# Modular_RFPA_v104.net
KiCad netlist of a schematic drawn in EAGLE
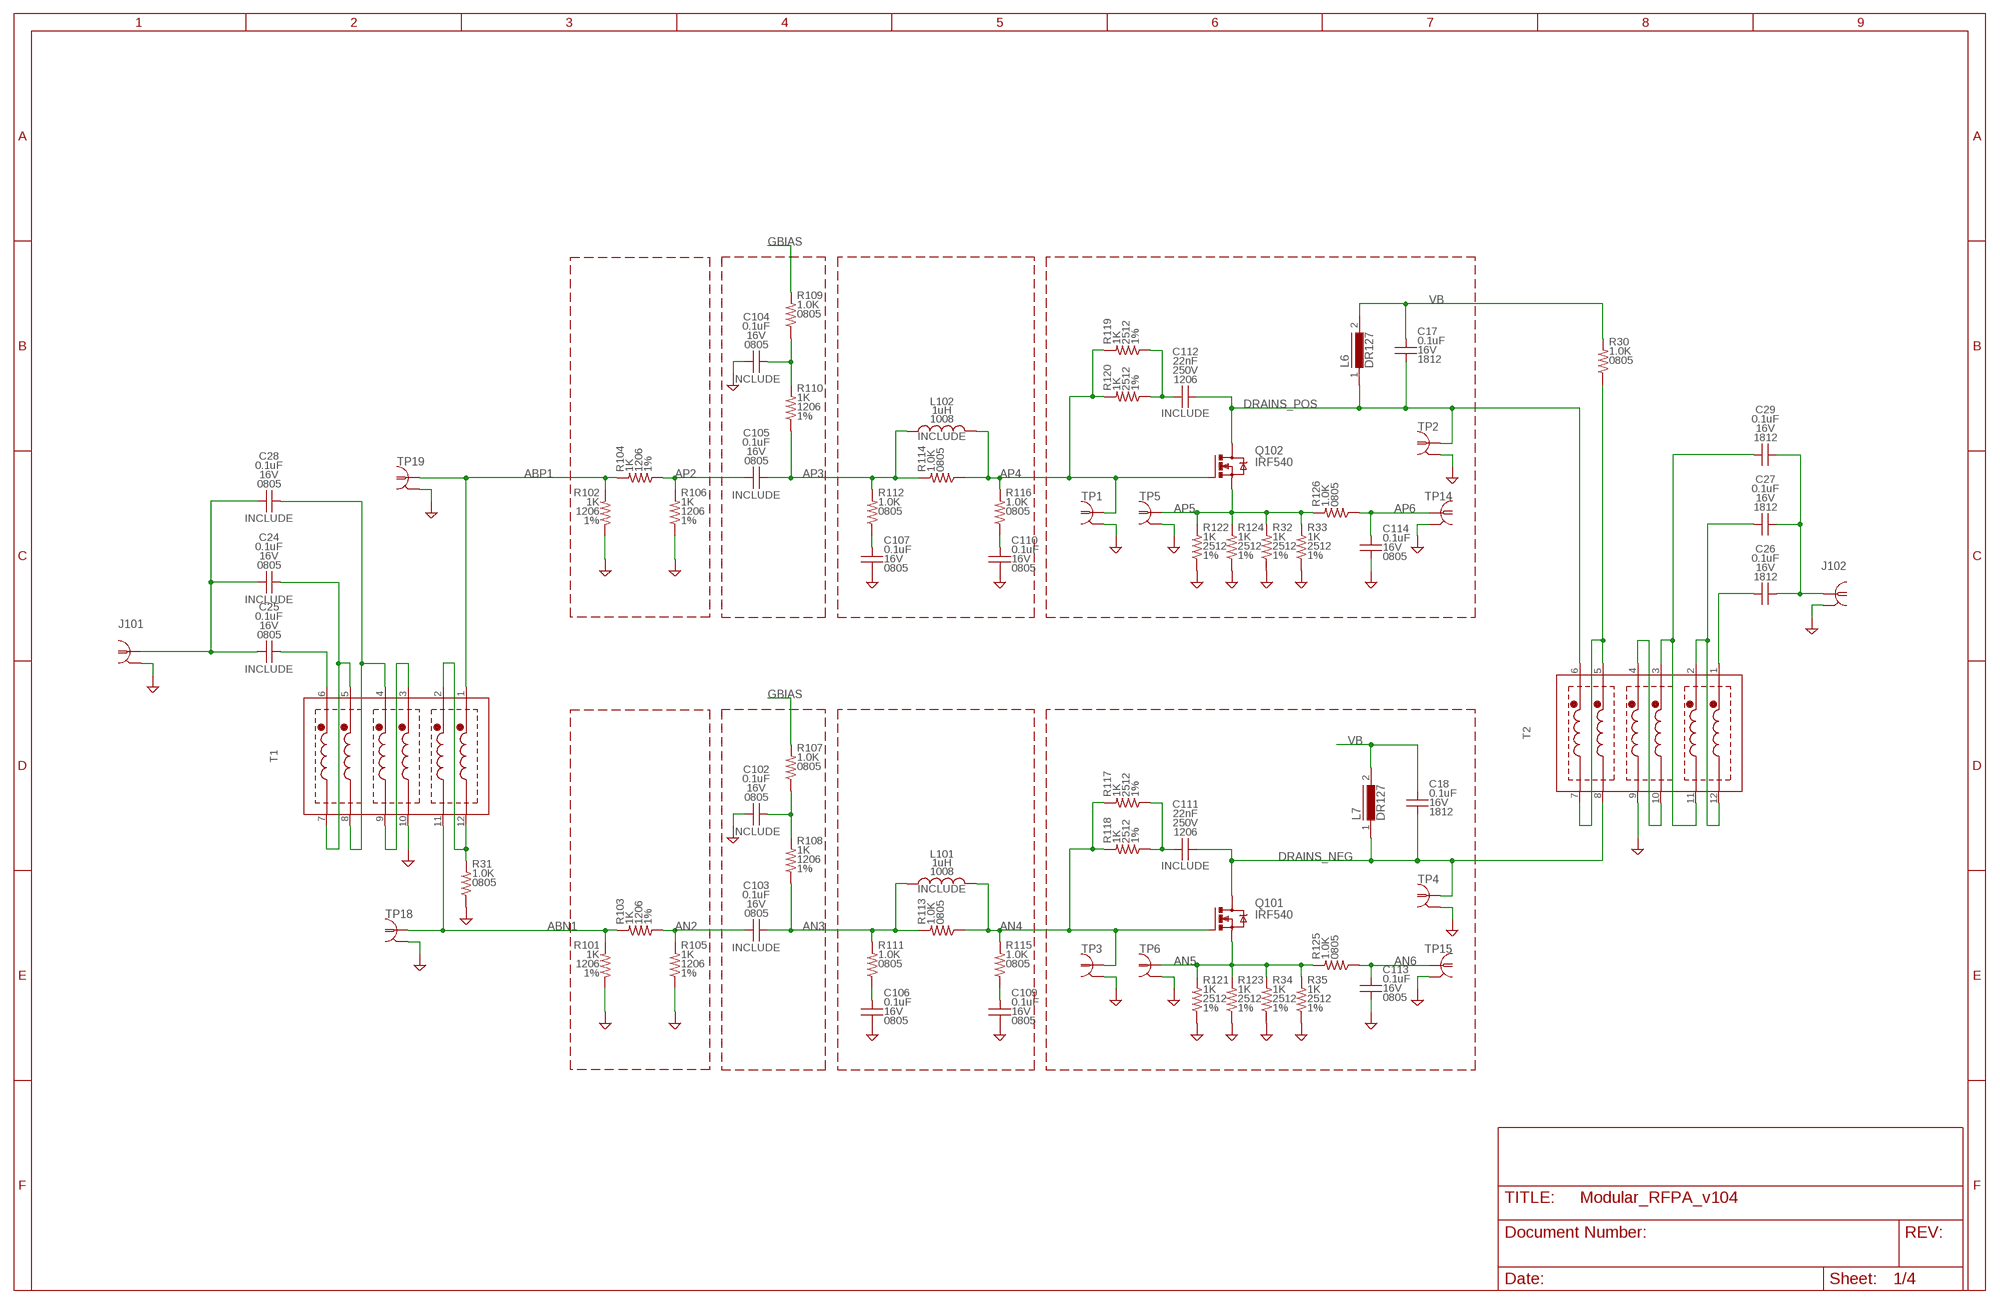
[diagram p0: schematic, sheet 1]
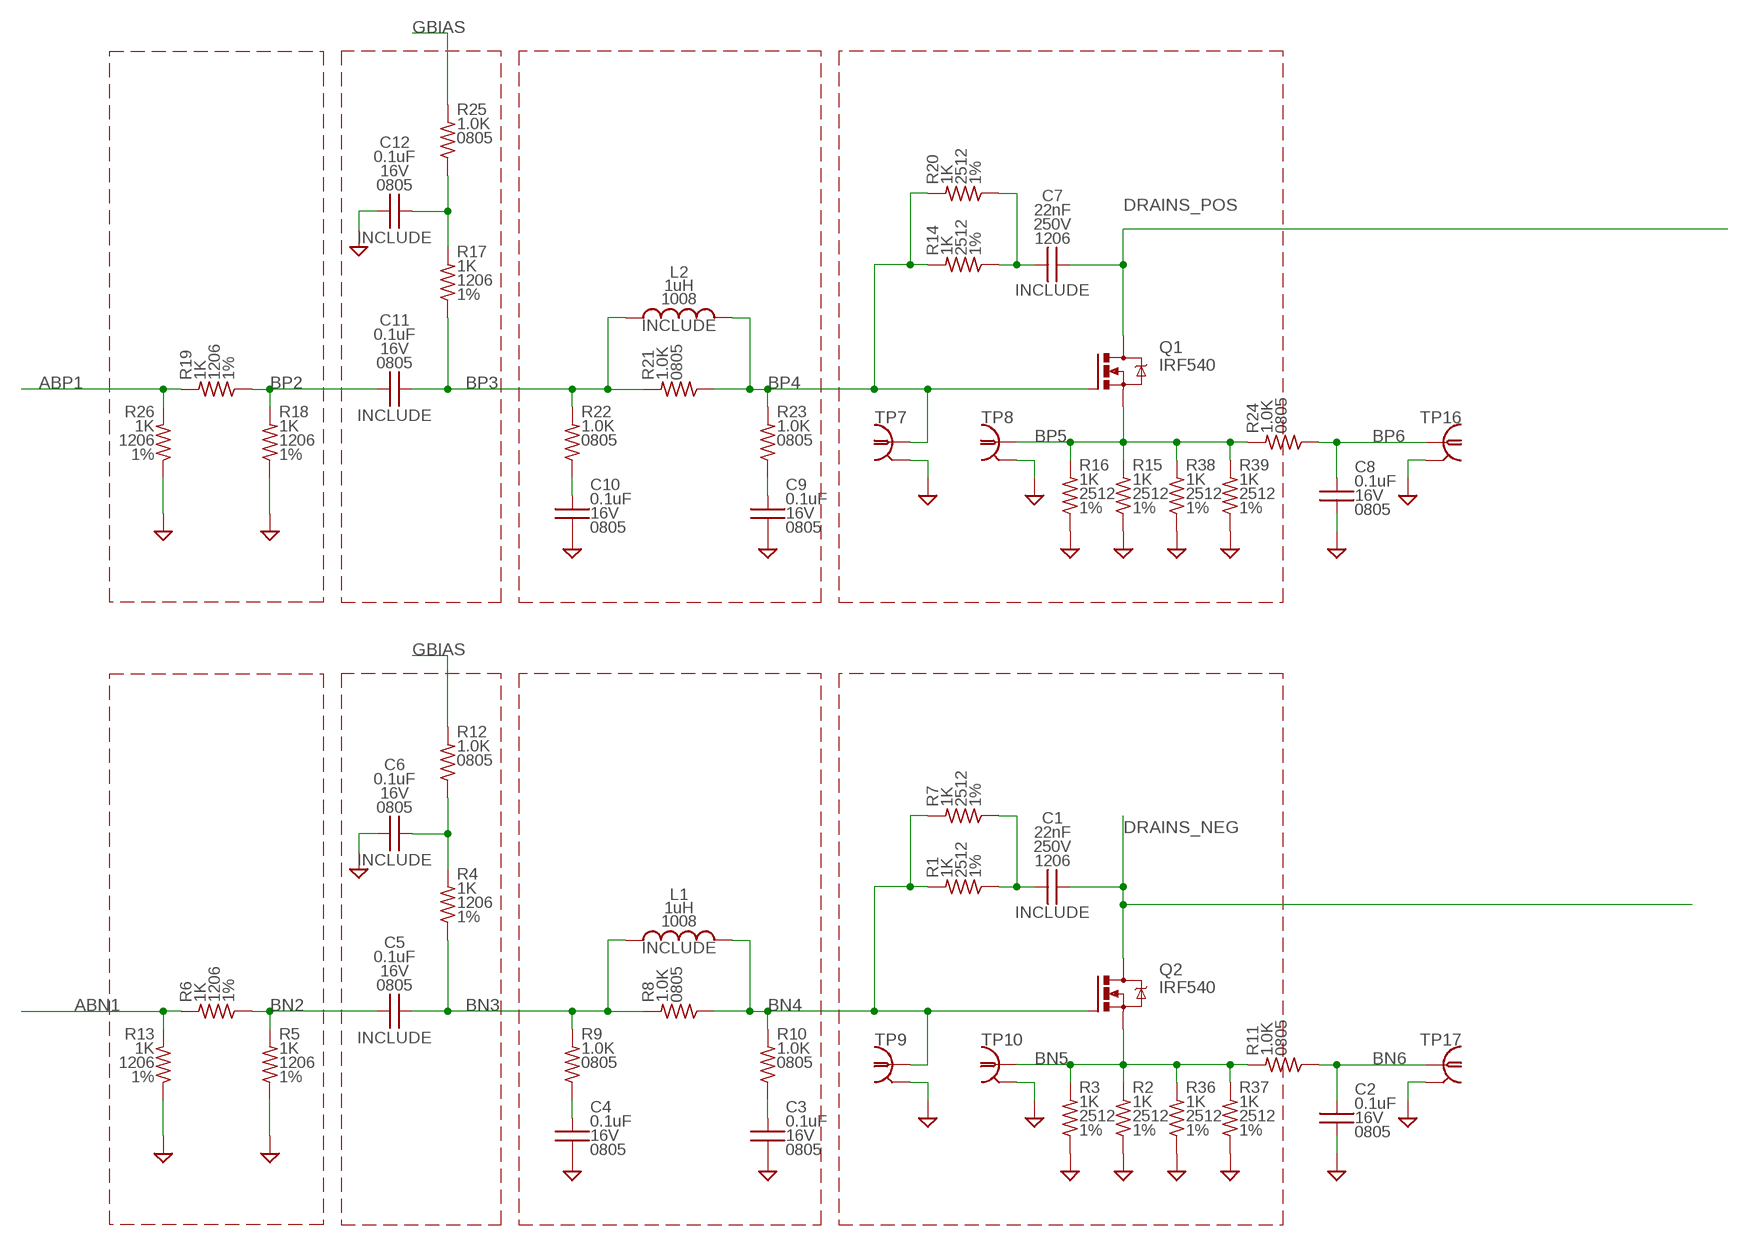
[diagram p1: schematic, sheet 2]
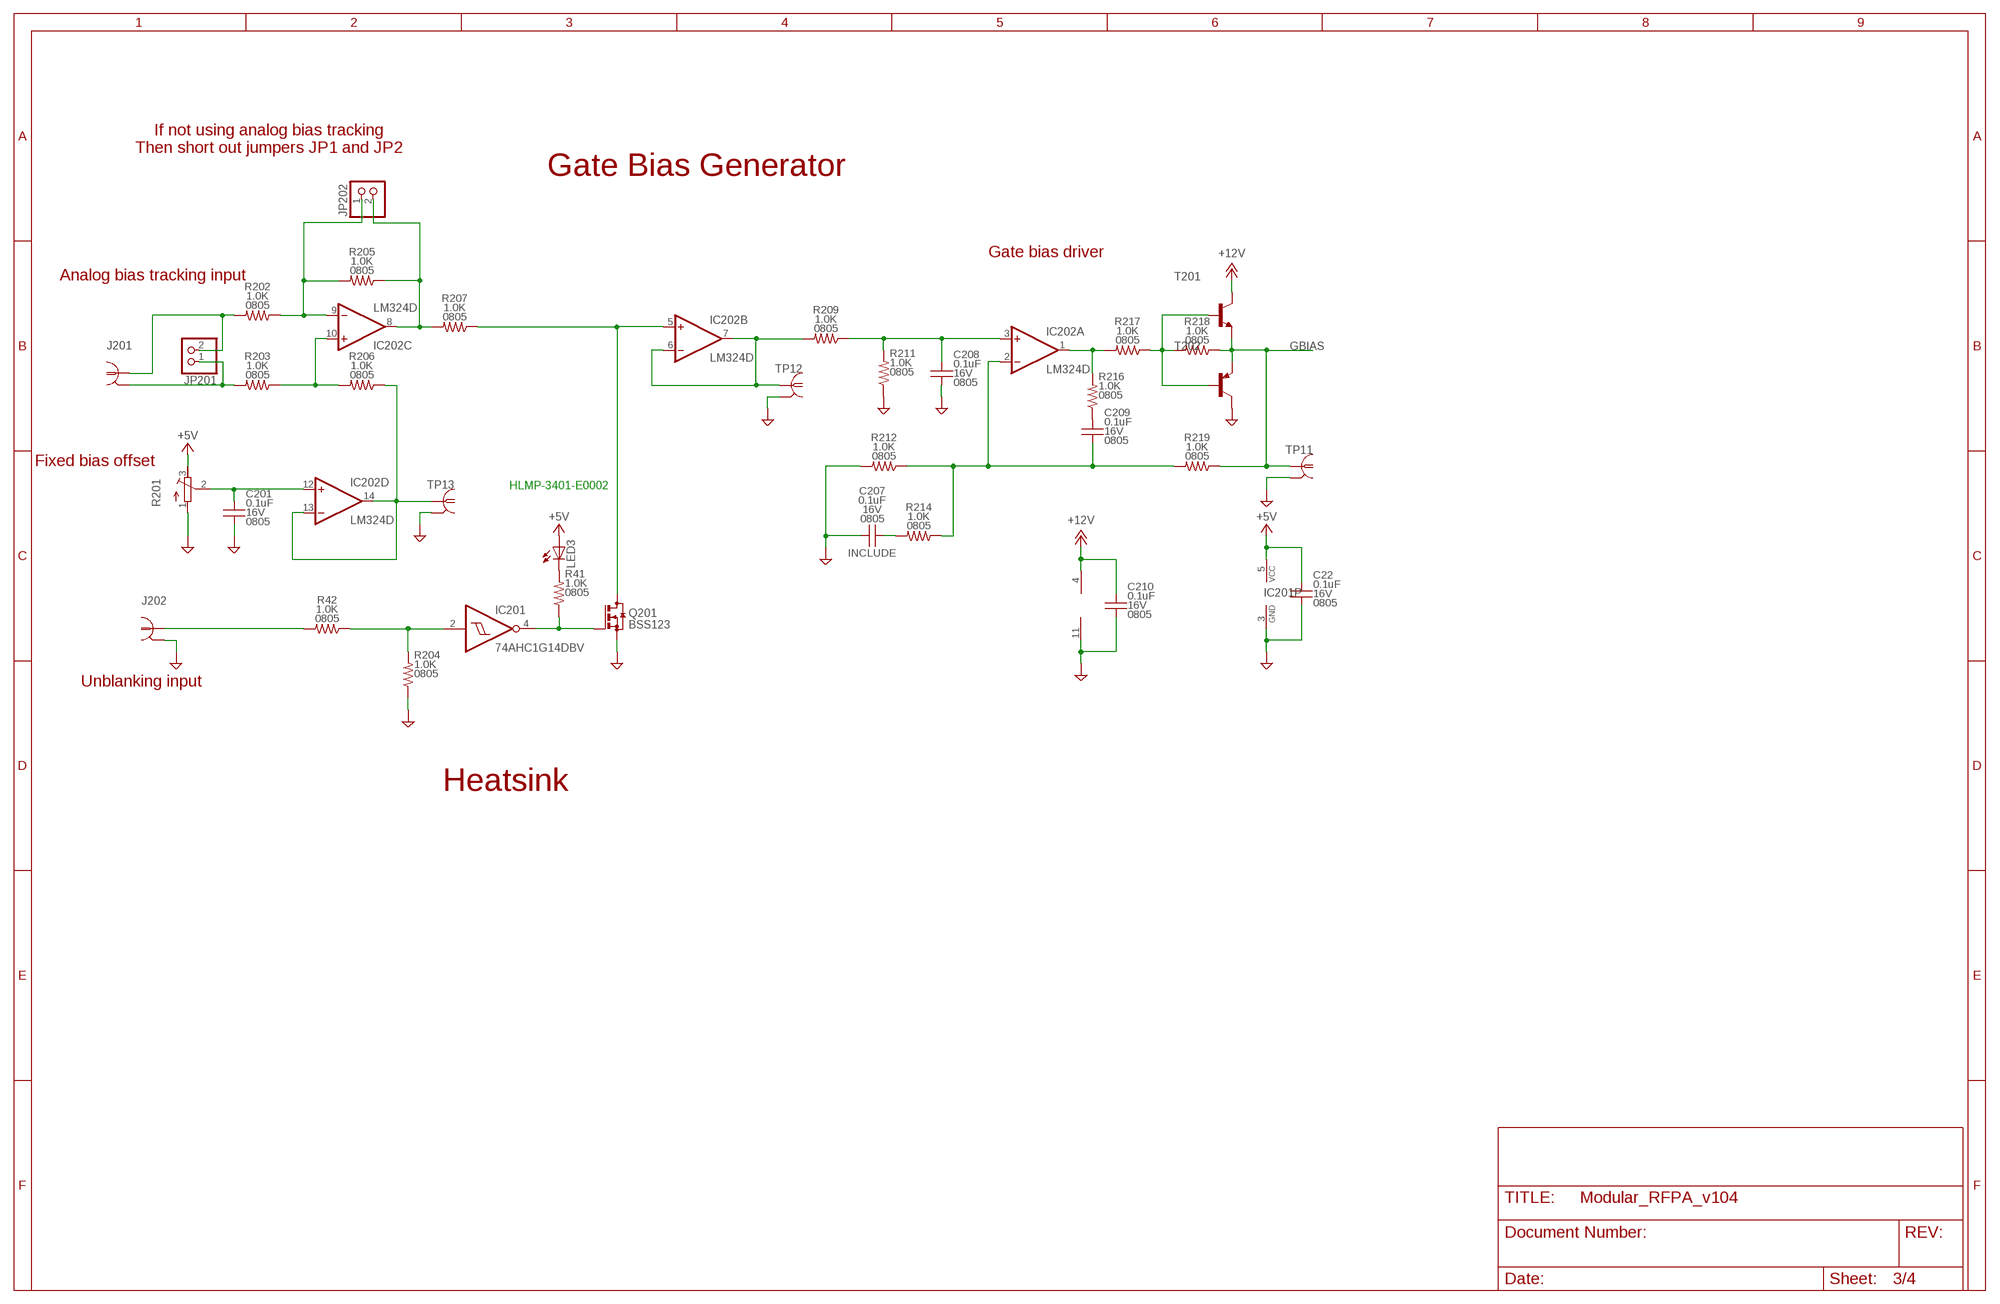
[diagram p2: schematic, sheet 3]
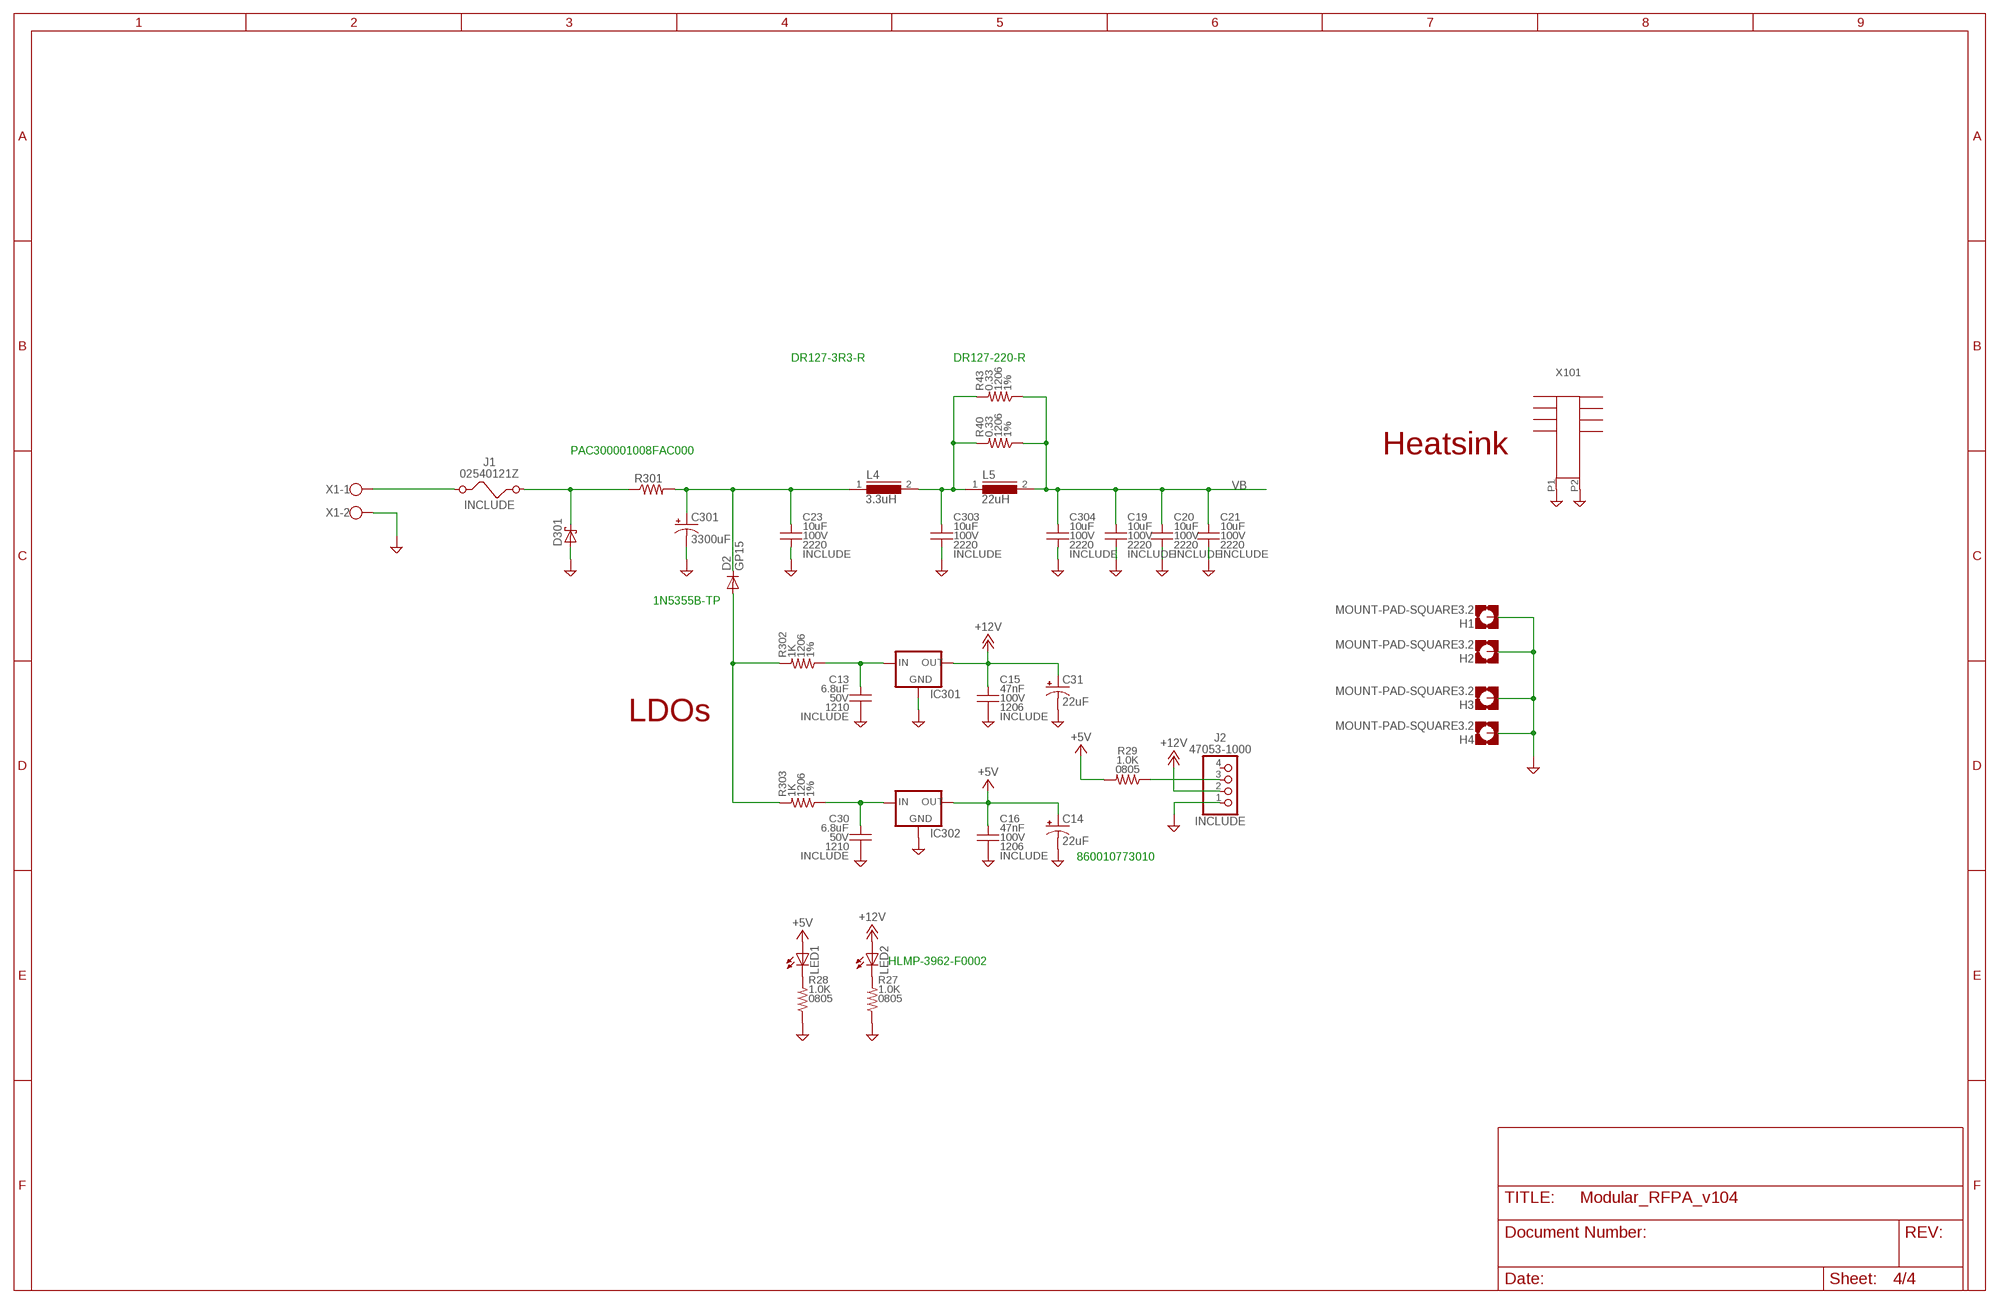
[diagram p3: schematic, sheet 4]

(export (version "E")
  (design (tool "Eeschema 10.0.6"))
  (components
    (comp (ref "C22")
      (value "0.1uF")
      (footprint "eagle-import:0805_IPC-7351B")
      (fields (field (name "VOLTAGE") "16V"))
      (libsource (lib "eagle-import") (part "C0805_IPCC-0.1U-16V-0805-X7R"))
    )
    (comp (ref "C201")
      (value "0.1uF")
      (footprint "eagle-import:0805_IPC-7351B")
      (fields (field (name "VOLTAGE") "16V"))
      (libsource (lib "eagle-import") (part "C0805_IPCC-0.1U-16V-0805-X7R"))
    )
    (comp (ref "C207")
      (value "0.1uF")
      (footprint "eagle-import:0805_IPC-7351B")
      (fields (field (name "PACKAGE") "0805") (field (name "VOLTAGE") "16V") (field (name "BOM") "INCLUDE"))
      (libsource (lib "eagle-import") (part "C0805_IPCC-0.1U-16V-0805-X7R"))
    )
    (comp (ref "C208")
      (value "0.1uF")
      (footprint "eagle-import:0805_IPC-7351B")
      (fields (field (name "VOLTAGE") "16V"))
      (libsource (lib "eagle-import") (part "C0805_IPCC-0.1U-16V-0805-X7R"))
    )
    (comp (ref "C209")
      (value "0.1uF")
      (footprint "eagle-import:0805_IPC-7351B")
      (fields (field (name "VOLTAGE") "16V"))
      (libsource (lib "eagle-import") (part "C0805_IPCC-0.1U-16V-0805-X7R"))
    )
    (comp (ref "C210")
      (value "0.1uF")
      (footprint "eagle-import:0805_IPC-7351B")
      (fields (field (name "VOLTAGE") "16V"))
      (libsource (lib "eagle-import") (part "C0805_IPCC-0.1U-16V-0805-X7R"))
    )
    (comp (ref "IC201")
      (value "74AHC1G14DBV")
      (footprint "eagle-import:SOT23-5")
      (libsource (lib "eagle-import") (part "741G14DBVAHC"))
    )
    (comp (ref "IC202")
      (value "LM324D")
      (footprint "eagle-import:SO14")
      (libsource (lib "eagle-import") (part "LM324D"))
    )
    (comp (ref "J201")
      (value "COAXBNC_EDGE")
      (footprint "eagle-import:BNC_EDGE")
      (libsource (lib "eagle-import") (part "COAXBNC_EDGE"))
    )
    (comp (ref "J202")
      (value "COAXBNC_EDGE")
      (footprint "eagle-import:BNC_EDGE")
      (libsource (lib "eagle-import") (part "COAXBNC_EDGE"))
    )
    (comp (ref "JP201")
      (value "PINHD-1X2")
      (footprint "eagle-import:1X02")
      (libsource (lib "eagle-import") (part "PINHD-1X2"))
    )
    (comp (ref "JP202")
      (value "PINHD-1X2")
      (footprint "eagle-import:1X02")
      (libsource (lib "eagle-import") (part "PINHD-1X2"))
    )
    (comp (ref "LED3")
      (value "LED5MM")
      (footprint "eagle-import:LED5MM")
      (libsource (lib "eagle-import") (part "LED5MM"))
    )
    (comp (ref "Q201")
      (value "BSS123")
      (footprint "eagle-import:SOT23")
      (libsource (lib "eagle-import") (part "BSS123"))
    )
    (comp (ref "R41")
      (value "1.0K")
      (footprint "eagle-import:0805_IPC-7351B")
      (libsource (lib "eagle-import") (part "R0805_IPCR-1.0K-0.1%-0805-0.1W"))
    )
    (comp (ref "R42")
      (value "1.0K")
      (footprint "eagle-import:0805_IPC-7351B")
      (fields (field (name "PACKAGE") "0805"))
      (libsource (lib "eagle-import") (part "R0805_IPCR-1.0K-0.1%-0805-0.1W"))
    )
    (comp (ref "R201")
      (value "R-TRIMM3299W")
      (footprint "eagle-import:RTRIM3299W")
      (libsource (lib "eagle-import") (part "R-TRIMM3299W"))
    )
    (comp (ref "R202")
      (value "1.0K")
      (footprint "eagle-import:0805_IPC-7351B")
      (fields (field (name "PACKAGE") "0805"))
      (libsource (lib "eagle-import") (part "R0805_IPCR-1.0K-0.1%-0805-0.1W"))
    )
    (comp (ref "R203")
      (value "1.0K")
      (footprint "eagle-import:0805_IPC-7351B")
      (fields (field (name "PACKAGE") "0805"))
      (libsource (lib "eagle-import") (part "R0805_IPCR-1.0K-0.1%-0805-0.1W"))
    )
    (comp (ref "R204")
      (value "1.0K")
      (footprint "eagle-import:0805_IPC-7351B")
      (libsource (lib "eagle-import") (part "R0805_IPCR-1.0K-0.1%-0805-0.1W"))
    )
    (comp (ref "R205")
      (value "1.0K")
      (footprint "eagle-import:0805_IPC-7351B")
      (fields (field (name "PACKAGE") "0805"))
      (libsource (lib "eagle-import") (part "R0805_IPCR-1.0K-0.1%-0805-0.1W"))
    )
    (comp (ref "R206")
      (value "1.0K")
      (footprint "eagle-import:0805_IPC-7351B")
      (fields (field (name "PACKAGE") "0805"))
      (libsource (lib "eagle-import") (part "R0805_IPCR-1.0K-0.1%-0805-0.1W"))
    )
    (comp (ref "R207")
      (value "1.0K")
      (footprint "eagle-import:0805_IPC-7351B")
      (fields (field (name "PACKAGE") "0805"))
      (libsource (lib "eagle-import") (part "R0805_IPCR-1.0K-0.1%-0805-0.1W"))
    )
    (comp (ref "R209")
      (value "1.0K")
      (footprint "eagle-import:0805_IPC-7351B")
      (fields (field (name "PACKAGE") "0805"))
      (libsource (lib "eagle-import") (part "R0805_IPCR-1.0K-0.1%-0805-0.1W"))
    )
    (comp (ref "R211")
      (value "1.0K")
      (footprint "eagle-import:0805_IPC-7351B")
      (libsource (lib "eagle-import") (part "R0805_IPCR-1.0K-0.1%-0805-0.1W"))
    )
    (comp (ref "R212")
      (value "1.0K")
      (footprint "eagle-import:0805_IPC-7351B")
      (fields (field (name "PACKAGE") "0805"))
      (libsource (lib "eagle-import") (part "R0805_IPCR-1.0K-0.1%-0805-0.1W"))
    )
    (comp (ref "R214")
      (value "1.0K")
      (footprint "eagle-import:0805_IPC-7351B")
      (fields (field (name "PACKAGE") "0805"))
      (libsource (lib "eagle-import") (part "R0805_IPCR-1.0K-0.1%-0805-0.1W"))
    )
    (comp (ref "R216")
      (value "1.0K")
      (footprint "eagle-import:0805_IPC-7351B")
      (libsource (lib "eagle-import") (part "R0805_IPCR-1.0K-0.1%-0805-0.1W"))
    )
    (comp (ref "R217")
      (value "1.0K")
      (footprint "eagle-import:0805_IPC-7351B")
      (fields (field (name "PACKAGE") "0805"))
      (libsource (lib "eagle-import") (part "R0805_IPCR-1.0K-0.1%-0805-0.1W"))
    )
    (comp (ref "R218")
      (value "1.0K")
      (footprint "eagle-import:0805_IPC-7351B")
      (fields (field (name "PACKAGE") "0805"))
      (libsource (lib "eagle-import") (part "R0805_IPCR-1.0K-0.1%-0805-0.1W"))
    )
    (comp (ref "R219")
      (value "1.0K")
      (footprint "eagle-import:0805_IPC-7351B")
      (fields (field (name "PACKAGE") "0805"))
      (libsource (lib "eagle-import") (part "R0805_IPCR-1.0K-0.1%-0805-0.1W"))
    )
    (comp (ref "T201")
      (value "BC808-NPN-SOT23-BEC")
      (footprint "eagle-import:SOT23-BEC")
      (libsource (lib "eagle-import") (part "-NPN-SOT23-BECBC808"))
    )
    (comp (ref "T202")
      (value "BC807-16-PNP-SOT23-BEC")
      (footprint "eagle-import:SOT23-BEC")
      (libsource (lib "eagle-import") (part "-PNP-SOT23-BECBC807-16"))
    )
    (comp (ref "TP11")
      (value "PROBE_TPTP_5MM")
      (footprint "eagle-import:PROBE_TP_5MM")
      (libsource (lib "eagle-import") (part "PROBE_TPTP_5MM"))
    )
    (comp (ref "TP12")
      (value "PROBE_TPTP_5MM")
      (footprint "eagle-import:PROBE_TP_5MM")
      (libsource (lib "eagle-import") (part "PROBE_TPTP_5MM"))
    )
    (comp (ref "TP13")
      (value "PROBE_TPTP_5MM")
      (footprint "eagle-import:PROBE_TP_5MM")
      (libsource (lib "eagle-import") (part "PROBE_TPTP_5MM"))
    )
    (comp (ref "C1")
      (value "22nF")
      (footprint "eagle-import:C1206")
      (fields
        (field (name "BOM") "INCLUDE")
        (field (name "PACKAGE") "1206")
        (field (name "PARTNO") "C3216NP02E223J160AA")
        (field (name "VOLTAGE") "250V")
      )
      (libsource (lib "eagle-import") (part "CC1206C-22N-250V-5%-1206-NP0"))
    )
    (comp (ref "C2")
      (value "0.1uF")
      (footprint "eagle-import:0805_IPC-7351B")
      (fields (field (name "VOLTAGE") "16V"))
      (libsource (lib "eagle-import") (part "C0805_IPCC-0.1U-16V-0805-X7R"))
    )
    (comp (ref "C3")
      (value "0.1uF")
      (footprint "eagle-import:0805_IPC-7351B")
      (fields (field (name "VOLTAGE") "16V"))
      (libsource (lib "eagle-import") (part "C0805_IPCC-0.1U-16V-0805-X7R"))
    )
    (comp (ref "C4")
      (value "0.1uF")
      (footprint "eagle-import:0805_IPC-7351B")
      (fields (field (name "VOLTAGE") "16V"))
      (libsource (lib "eagle-import") (part "C0805_IPCC-0.1U-16V-0805-X7R"))
    )
    (comp (ref "C5")
      (value "0.1uF")
      (footprint "eagle-import:0805_IPC-7351B")
      (fields (field (name "PACKAGE") "0805") (field (name "VOLTAGE") "16V") (field (name "BOM") "INCLUDE"))
      (libsource (lib "eagle-import") (part "C0805_IPCC-0.1U-16V-0805-X7R"))
    )
    (comp (ref "C6")
      (value "0.1uF")
      (footprint "eagle-import:0805_IPC-7351B")
      (fields (field (name "PACKAGE") "0805") (field (name "VOLTAGE") "16V") (field (name "BOM") "INCLUDE"))
      (libsource (lib "eagle-import") (part "C0805_IPCC-0.1U-16V-0805-X7R"))
    )
    (comp (ref "C7")
      (value "22nF")
      (footprint "eagle-import:C1206")
      (fields
        (field (name "BOM") "INCLUDE")
        (field (name "PACKAGE") "1206")
        (field (name "PARTNO") "C3216NP02E223J160AA")
        (field (name "VOLTAGE") "250V")
      )
      (libsource (lib "eagle-import") (part "CC1206C-22N-250V-5%-1206-NP0"))
    )
    (comp (ref "C8")
      (value "0.1uF")
      (footprint "eagle-import:0805_IPC-7351B")
      (fields (field (name "VOLTAGE") "16V"))
      (libsource (lib "eagle-import") (part "C0805_IPCC-0.1U-16V-0805-X7R"))
    )
    (comp (ref "C9")
      (value "0.1uF")
      (footprint "eagle-import:0805_IPC-7351B")
      (fields (field (name "VOLTAGE") "16V"))
      (libsource (lib "eagle-import") (part "C0805_IPCC-0.1U-16V-0805-X7R"))
    )
    (comp (ref "C10")
      (value "0.1uF")
      (footprint "eagle-import:0805_IPC-7351B")
      (fields (field (name "VOLTAGE") "16V"))
      (libsource (lib "eagle-import") (part "C0805_IPCC-0.1U-16V-0805-X7R"))
    )
    (comp (ref "C11")
      (value "0.1uF")
      (footprint "eagle-import:0805_IPC-7351B")
      (fields (field (name "PACKAGE") "0805") (field (name "VOLTAGE") "16V") (field (name "BOM") "INCLUDE"))
      (libsource (lib "eagle-import") (part "C0805_IPCC-0.1U-16V-0805-X7R"))
    )
    (comp (ref "C12")
      (value "0.1uF")
      (footprint "eagle-import:0805_IPC-7351B")
      (fields (field (name "PACKAGE") "0805") (field (name "VOLTAGE") "16V") (field (name "BOM") "INCLUDE"))
      (libsource (lib "eagle-import") (part "C0805_IPCC-0.1U-16V-0805-X7R"))
    )
    (comp (ref "L1")
      (value "1uH")
      (footprint "eagle-import:L1008")
      (fields (field (name "PARTNO") "1008CS-102XJEC"))
      (libsource (lib "eagle-import") (part "L_CHIP1008L-1.0U-AIR-5%-1008-0.37A"))
    )
    (comp (ref "L2")
      (value "1uH")
      (footprint "eagle-import:L1008")
      (fields (field (name "PARTNO") "1008CS-102XJEC"))
      (libsource (lib "eagle-import") (part "L_CHIP1008L-1.0U-AIR-5%-1008-0.37A"))
    )
    (comp (ref "Q1")
      (value "IRF540")
      (footprint "eagle-import:TO220BV")
      (libsource (lib "eagle-import") (part "IRF540"))
    )
    (comp (ref "Q2")
      (value "IRF540")
      (footprint "eagle-import:TO220BV")
      (libsource (lib "eagle-import") (part "IRF540"))
    )
    (comp (ref "R1")
      (value "1K")
      (footprint "eagle-import:R2512")
      (fields (field (name "POWER") "1"))
      (libsource (lib "eagle-import") (part "RR2512R-1K-1%-2512-1W"))
    )
    (comp (ref "R2")
      (value "1K")
      (footprint "eagle-import:R2512")
      (fields (field (name "POWER") "1"))
      (libsource (lib "eagle-import") (part "RR2512R-1K-1%-2512-1W"))
    )
    (comp (ref "R3")
      (value "1K")
      (footprint "eagle-import:R2512")
      (fields (field (name "POWER") "1"))
      (libsource (lib "eagle-import") (part "RR2512R-1K-1%-2512-1W"))
    )
    (comp (ref "R4")
      (value "1K")
      (footprint "eagle-import:R1206")
      (fields (field (name "POWER") "0.25"))
      (libsource (lib "eagle-import") (part "RR1206R-1.0K-1%-1206-0.25W"))
    )
    (comp (ref "R5")
      (value "1K")
      (footprint "eagle-import:R1206")
      (fields (field (name "POWER") "0.25"))
      (libsource (lib "eagle-import") (part "RR1206R-1.0K-1%-1206-0.25W"))
    )
    (comp (ref "R6")
      (value "1K")
      (footprint "eagle-import:R1206")
      (fields (field (name "POWER") "0.25"))
      (libsource (lib "eagle-import") (part "RR1206R-1.0K-1%-1206-0.25W"))
    )
    (comp (ref "R7")
      (value "1K")
      (footprint "eagle-import:R2512")
      (fields (field (name "POWER") "1"))
      (libsource (lib "eagle-import") (part "RR2512R-1K-1%-2512-1W"))
    )
    (comp (ref "R8")
      (value "1.0K")
      (footprint "eagle-import:0805_IPC-7351B")
      (libsource (lib "eagle-import") (part "R0805_IPCR-1.0K-0.1%-0805-0.1W"))
    )
    (comp (ref "R9")
      (value "1.0K")
      (footprint "eagle-import:0805_IPC-7351B")
      (libsource (lib "eagle-import") (part "R0805_IPCR-1.0K-0.1%-0805-0.1W"))
    )
    (comp (ref "R10")
      (value "1.0K")
      (footprint "eagle-import:0805_IPC-7351B")
      (libsource (lib "eagle-import") (part "R0805_IPCR-1.0K-0.1%-0805-0.1W"))
    )
    (comp (ref "R11")
      (value "1.0K")
      (footprint "eagle-import:0805_IPC-7351B")
      (libsource (lib "eagle-import") (part "R0805_IPCR-1.0K-0.1%-0805-0.1W"))
    )
    (comp (ref "R12")
      (value "1.0K")
      (footprint "eagle-import:0805_IPC-7351B")
      (libsource (lib "eagle-import") (part "R0805_IPCR-1.0K-0.1%-0805-0.1W"))
    )
    (comp (ref "R13")
      (value "1K")
      (footprint "eagle-import:R1206")
      (fields (field (name "POWER") "0.25"))
      (libsource (lib "eagle-import") (part "RR1206R-1.0K-1%-1206-0.25W"))
    )
    (comp (ref "R14")
      (value "1K")
      (footprint "eagle-import:R2512")
      (fields (field (name "POWER") "1"))
      (libsource (lib "eagle-import") (part "RR2512R-1K-1%-2512-1W"))
    )
    (comp (ref "R15")
      (value "1K")
      (footprint "eagle-import:R2512")
      (fields (field (name "POWER") "1"))
      (libsource (lib "eagle-import") (part "RR2512R-1K-1%-2512-1W"))
    )
    (comp (ref "R16")
      (value "1K")
      (footprint "eagle-import:R2512")
      (fields (field (name "POWER") "1"))
      (libsource (lib "eagle-import") (part "RR2512R-1K-1%-2512-1W"))
    )
    (comp (ref "R17")
      (value "1K")
      (footprint "eagle-import:R1206")
      (fields (field (name "POWER") "0.25"))
      (libsource (lib "eagle-import") (part "RR1206R-1.0K-1%-1206-0.25W"))
    )
    (comp (ref "R18")
      (value "1K")
      (footprint "eagle-import:R1206")
      (fields (field (name "POWER") "0.25"))
      (libsource (lib "eagle-import") (part "RR1206R-1.0K-1%-1206-0.25W"))
    )
    (comp (ref "R19")
      (value "1K")
      (footprint "eagle-import:R1206")
      (fields (field (name "POWER") "0.25"))
      (libsource (lib "eagle-import") (part "RR1206R-1.0K-1%-1206-0.25W"))
    )
    (comp (ref "R20")
      (value "1K")
      (footprint "eagle-import:R2512")
      (fields (field (name "POWER") "1"))
      (libsource (lib "eagle-import") (part "RR2512R-1K-1%-2512-1W"))
    )
    (comp (ref "R21")
      (value "1.0K")
      (footprint "eagle-import:0805_IPC-7351B")
      (libsource (lib "eagle-import") (part "R0805_IPCR-1.0K-0.1%-0805-0.1W"))
    )
    (comp (ref "R22")
      (value "1.0K")
      (footprint "eagle-import:0805_IPC-7351B")
      (libsource (lib "eagle-import") (part "R0805_IPCR-1.0K-0.1%-0805-0.1W"))
    )
    (comp (ref "R23")
      (value "1.0K")
      (footprint "eagle-import:0805_IPC-7351B")
      (libsource (lib "eagle-import") (part "R0805_IPCR-1.0K-0.1%-0805-0.1W"))
    )
    (comp (ref "R24")
      (value "1.0K")
      (footprint "eagle-import:0805_IPC-7351B")
      (libsource (lib "eagle-import") (part "R0805_IPCR-1.0K-0.1%-0805-0.1W"))
    )
    (comp (ref "R25")
      (value "1.0K")
      (footprint "eagle-import:0805_IPC-7351B")
      (libsource (lib "eagle-import") (part "R0805_IPCR-1.0K-0.1%-0805-0.1W"))
    )
    (comp (ref "R26")
      (value "1K")
      (footprint "eagle-import:R1206")
      (fields (field (name "POWER") "0.25"))
      (libsource (lib "eagle-import") (part "RR1206R-1.0K-1%-1206-0.25W"))
    )
    (comp (ref "R36")
      (value "1K")
      (footprint "eagle-import:R2512")
      (fields (field (name "POWER") "1"))
      (libsource (lib "eagle-import") (part "RR2512R-1K-1%-2512-1W"))
    )
    (comp (ref "R37")
      (value "1K")
      (footprint "eagle-import:R2512")
      (fields (field (name "POWER") "1"))
      (libsource (lib "eagle-import") (part "RR2512R-1K-1%-2512-1W"))
    )
    (comp (ref "R38")
      (value "1K")
      (footprint "eagle-import:R2512")
      (fields (field (name "POWER") "1"))
      (libsource (lib "eagle-import") (part "RR2512R-1K-1%-2512-1W"))
    )
    (comp (ref "R39")
      (value "1K")
      (footprint "eagle-import:R2512")
      (fields (field (name "POWER") "1"))
      (libsource (lib "eagle-import") (part "RR2512R-1K-1%-2512-1W"))
    )
    (comp (ref "TP7")
      (value "PROBE_TPTP_5MM")
      (footprint "eagle-import:PROBE_TP_5MM")
      (libsource (lib "eagle-import") (part "PROBE_TPTP_5MM"))
    )
    (comp (ref "TP8")
      (value "PROBE_TPTP_7P5MM")
      (footprint "eagle-import:PROBE_TP_7P5MM")
      (libsource (lib "eagle-import") (part "PROBE_TPTP_7P5MM"))
    )
    (comp (ref "TP9")
      (value "PROBE_TPTP_5MM")
      (footprint "eagle-import:PROBE_TP_5MM")
      (libsource (lib "eagle-import") (part "PROBE_TPTP_5MM"))
    )
    (comp (ref "TP10")
      (value "PROBE_TPTP_5MM")
      (footprint "eagle-import:PROBE_TP_5MM")
      (libsource (lib "eagle-import") (part "PROBE_TPTP_5MM"))
    )
    (comp (ref "TP16")
      (value "PROBE_TPTP_5MM")
      (footprint "eagle-import:PROBE_TP_5MM")
      (libsource (lib "eagle-import") (part "PROBE_TPTP_5MM"))
    )
    (comp (ref "TP17")
      (value "PROBE_TPTP_7P5MM")
      (footprint "eagle-import:PROBE_TP_7P5MM")
      (libsource (lib "eagle-import") (part "PROBE_TPTP_7P5MM"))
    )
    (comp (ref "C13")
      (value "6.8uF")
      (footprint "eagle-import:C1210")
      (fields (field (name "PARTNO") "CGA6P3X7S1H685K250AB") (field (name "VOLTAGE") "50V"))
      (libsource (lib "eagle-import") (part "CC1210CC-6.8U-50V-10%-1210-X7S"))
    )
    (comp (ref "C14")
      (value "22uF")
      (footprint "eagle-import:E2,5-7")
      (libsource (lib "eagle-import") (part "CPOL-USE2.5-7"))
    )
    (comp (ref "C15")
      (value "47nF")
      (footprint "eagle-import:C1206")
      (fields (field (name "PARTNO") "C3216C0G2A473J115AC") (field (name "VOLTAGE") "100V"))
      (libsource (lib "eagle-import") (part "CC1206C-47N-100V-5%-1206-NP0"))
    )
    (comp (ref "C16")
      (value "47nF")
      (footprint "eagle-import:C1206")
      (fields (field (name "PARTNO") "C3216C0G2A473J115AC") (field (name "VOLTAGE") "100V"))
      (libsource (lib "eagle-import") (part "CC1206C-47N-100V-5%-1206-NP0"))
    )
    (comp (ref "C19")
      (value "10uF")
      (footprint "eagle-import:C2220_CKG57N")
      (fields (field (name "PARTNO") "CGA9N3X7S2A106M230KE") (field (name "VOLTAGE") "100V"))
      (libsource (lib "eagle-import") (part "CC2220_CKG57NCC-10U-100V-20%-2220-X7T"))
    )
    (comp (ref "C20")
      (value "10uF")
      (footprint "eagle-import:C2220_CKG57N")
      (fields (field (name "PARTNO") "CGA9N3X7S2A106M230KE") (field (name "VOLTAGE") "100V"))
      (libsource (lib "eagle-import") (part "CC2220_CKG57NCC-10U-100V-20%-2220-X7T"))
    )
    (comp (ref "C21")
      (value "10uF")
      (footprint "eagle-import:C2220_CKG57N")
      (fields (field (name "PARTNO") "CGA9N3X7S2A106M230KE") (field (name "VOLTAGE") "100V"))
      (libsource (lib "eagle-import") (part "CC2220_CKG57NCC-10U-100V-20%-2220-X7T"))
    )
    (comp (ref "C23")
      (value "10uF")
      (footprint "eagle-import:C2220_CKG57N")
      (fields (field (name "PARTNO") "CGA9N3X7S2A106M230KE") (field (name "VOLTAGE") "100V"))
      (libsource (lib "eagle-import") (part "CC2220_CKG57NCC-10U-100V-20%-2220-X7T"))
    )
    (comp (ref "C30")
      (value "6.8uF")
      (footprint "eagle-import:C1210")
      (fields (field (name "PARTNO") "CGA6P3X7S1H685K250AB") (field (name "VOLTAGE") "50V"))
      (libsource (lib "eagle-import") (part "CC1210CC-6.8U-50V-10%-1210-X7S"))
    )
    (comp (ref "C31")
      (value "22uF")
      (footprint "eagle-import:E2,5-7")
      (libsource (lib "eagle-import") (part "CPOL-USE2.5-7"))
    )
    (comp (ref "C301")
      (value "3300uF")
      (footprint "eagle-import:EB25D")
      (libsource (lib "eagle-import") (part "CPOL-USE10-25"))
    )
    (comp (ref "C303")
      (value "10uF")
      (footprint "eagle-import:C2220_CKG57N")
      (fields (field (name "PARTNO") "CGA9N3X7S2A106M230KE") (field (name "VOLTAGE") "100V"))
      (libsource (lib "eagle-import") (part "CC2220_CKG57NCC-10U-100V-20%-2220-X7T"))
    )
    (comp (ref "C304")
      (value "10uF")
      (footprint "eagle-import:C2220_CKG57N")
      (fields (field (name "PARTNO") "CGA9N3X7S2A106M230KE") (field (name "VOLTAGE") "100V"))
      (libsource (lib "eagle-import") (part "CC2220_CKG57NCC-10U-100V-20%-2220-X7T"))
    )
    (comp (ref "D2")
      (value "GP15")
      (footprint "eagle-import:DO15-12")
      (libsource (lib "eagle-import") (part "GP15"))
    )
    (comp (ref "D301")
      (value "SCHOTTKY-DIODESMC")
      (footprint "eagle-import:SMC")
      (libsource (lib "eagle-import") (part "SCHOTTKY-DIODESMC"))
    )
    (comp (ref "H1")
      (value "MOUNT-PAD-SQUARE3.2")
      (footprint "eagle-import:3,2-PAD-SQUARE")
      (libsource (lib "eagle-import") (part "MOUNT-PAD-SQUARE3.2"))
    )
    (comp (ref "H2")
      (value "MOUNT-PAD-SQUARE3.2")
      (footprint "eagle-import:3,2-PAD-SQUARE")
      (libsource (lib "eagle-import") (part "MOUNT-PAD-SQUARE3.2"))
    )
    (comp (ref "H3")
      (value "MOUNT-PAD-SQUARE3.2")
      (footprint "eagle-import:3,2-PAD-SQUARE")
      (libsource (lib "eagle-import") (part "MOUNT-PAD-SQUARE3.2"))
    )
    (comp (ref "H4")
      (value "MOUNT-PAD-SQUARE3.2")
      (footprint "eagle-import:3,2-PAD-SQUARE")
      (libsource (lib "eagle-import") (part "MOUNT-PAD-SQUARE3.2"))
    )
    (comp (ref "IC301")
      (value "78XXS")
      (footprint "eagle-import:78XXS")
      (libsource (lib "eagle-import") (part "78XXS"))
    )
    (comp (ref "IC302")
      (value "78XXS")
      (footprint "eagle-import:78XXS")
      (libsource (lib "eagle-import") (part "78XXS"))
    )
    (comp (ref "J1")
      (value "FUSE_2P")
      (footprint "eagle-import:02540121Z")
      (fields (field (name "PARTNO") "02540121Z"))
      (libsource (lib "eagle-import") (part "FUSE_2P"))
    )
    (comp (ref "J2")
      (value "KK_PCFAN")
      (footprint "eagle-import:47053-1000")
      (fields (field (name "PARTNO") "47053-1000"))
      (libsource (lib "eagle-import") (part "KK_PCFAN"))
    )
    (comp (ref "L4")
      (value "3.3uH")
      (footprint "eagle-import:DR127")
      (libsource (lib "eagle-import") (part "DR127"))
    )
    (comp (ref "L5")
      (value "22uH")
      (footprint "eagle-import:DR127")
      (libsource (lib "eagle-import") (part "DR127"))
    )
    (comp (ref "LED1")
      (value "LED5MM")
      (footprint "eagle-import:LED5MM")
      (libsource (lib "eagle-import") (part "LED5MM"))
    )
    (comp (ref "LED2")
      (value "LED5MM")
      (footprint "eagle-import:LED5MM")
      (libsource (lib "eagle-import") (part "LED5MM"))
    )
    (comp (ref "R27")
      (value "1.0K")
      (footprint "eagle-import:0805_IPC-7351B")
      (libsource (lib "eagle-import") (part "R0805_IPCR-1.0K-0.1%-0805-0.1W"))
    )
    (comp (ref "R28")
      (value "1.0K")
      (footprint "eagle-import:0805_IPC-7351B")
      (libsource (lib "eagle-import") (part "R0805_IPCR-1.0K-0.1%-0805-0.1W"))
    )
    (comp (ref "R29")
      (value "1.0K")
      (footprint "eagle-import:0805_IPC-7351B")
      (fields (field (name "PACKAGE") "0805"))
      (libsource (lib "eagle-import") (part "R0805_IPCR-1.0K-0.1%-0805-0.1W"))
    )
    (comp (ref "R40")
      (value "0.33")
      (footprint "eagle-import:R1206")
      (fields (field (name "POWER") "0.25"))
      (libsource (lib "eagle-import") (part "RR1206R-1.0K-1%-1206-0.25W"))
    )
    (comp (ref "R43")
      (value "0.33")
      (footprint "eagle-import:R1206")
      (fields (field (name "POWER") "0.25"))
      (libsource (lib "eagle-import") (part "RR1206R-1.0K-1%-1206-0.25W"))
    )
    (comp (ref "R301")
      (value "R-US_0817/7V")
      (footprint "eagle-import:P0817V")
      (libsource (lib "eagle-import") (part "R-US_0817/7V"))
    )
    (comp (ref "R302")
      (value "1K")
      (footprint "eagle-import:R1206")
      (fields (field (name "POWER") "0.25"))
      (libsource (lib "eagle-import") (part "RR1206R-1.0K-1%-1206-0.25W"))
    )
    (comp (ref "R303")
      (value "1K")
      (footprint "eagle-import:R1206")
      (fields (field (name "POWER") "0.25"))
      (libsource (lib "eagle-import") (part "RR1206R-1.0K-1%-1206-0.25W"))
    )
    (comp (ref "X1")
      (value "W237-102")
      (footprint "eagle-import:W237-102")
      (fields (field (name "MPN") "237-102"))
      (libsource (lib "eagle-import") (part "W237-102"))
    )
    (comp (ref "X101")
      (value "HEATSINK_OMNI_DUAL30-75-D")
      (footprint "eagle-import:OMNI-UNI-30-75-D")
      (libsource (lib "eagle-import") (part "HEATSINK_OMNI_DUAL30-75-D"))
    )
    (comp (ref "C17")
      (value "0.1uF")
      (footprint "eagle-import:C1812")
      (fields (field (name "VOLTAGE") "16V"))
      (libsource (lib "eagle-import") (part "CC1812"))
    )
    (comp (ref "C18")
      (value "0.1uF")
      (footprint "eagle-import:C1812")
      (fields (field (name "VOLTAGE") "16V"))
      (libsource (lib "eagle-import") (part "CC1812"))
    )
    (comp (ref "C24")
      (value "0.1uF")
      (footprint "eagle-import:0805_IPC-7351B")
      (fields (field (name "PACKAGE") "0805") (field (name "VOLTAGE") "16V") (field (name "BOM") "INCLUDE"))
      (libsource (lib "eagle-import") (part "C0805_IPCC-0.1U-16V-0805-X7R"))
    )
    (comp (ref "C25")
      (value "0.1uF")
      (footprint "eagle-import:0805_IPC-7351B")
      (fields (field (name "PACKAGE") "0805") (field (name "VOLTAGE") "16V") (field (name "BOM") "INCLUDE"))
      (libsource (lib "eagle-import") (part "C0805_IPCC-0.1U-16V-0805-X7R"))
    )
    (comp (ref "C26")
      (value "0.1uF")
      (footprint "eagle-import:C1812")
      (fields (field (name "VOLTAGE") "16V") (field (name "PACKAGE") "1812"))
      (libsource (lib "eagle-import") (part "CC1812"))
    )
    (comp (ref "C27")
      (value "0.1uF")
      (footprint "eagle-import:C1812")
      (fields (field (name "VOLTAGE") "16V") (field (name "PACKAGE") "1812"))
      (libsource (lib "eagle-import") (part "CC1812"))
    )
    (comp (ref "C28")
      (value "0.1uF")
      (footprint "eagle-import:0805_IPC-7351B")
      (fields (field (name "PACKAGE") "0805") (field (name "VOLTAGE") "16V") (field (name "BOM") "INCLUDE"))
      (libsource (lib "eagle-import") (part "C0805_IPCC-0.1U-16V-0805-X7R"))
    )
    (comp (ref "C29")
      (value "0.1uF")
      (footprint "eagle-import:C1812")
      (fields (field (name "VOLTAGE") "16V") (field (name "PACKAGE") "1812"))
      (libsource (lib "eagle-import") (part "CC1812"))
    )
    (comp (ref "C102")
      (value "0.1uF")
      (footprint "eagle-import:0805_IPC-7351B")
      (fields (field (name "PACKAGE") "0805") (field (name "VOLTAGE") "16V") (field (name "BOM") "INCLUDE"))
      (libsource (lib "eagle-import") (part "C0805_IPCC-0.1U-16V-0805-X7R"))
    )
    (comp (ref "C103")
      (value "0.1uF")
      (footprint "eagle-import:0805_IPC-7351B")
      (fields (field (name "PACKAGE") "0805") (field (name "VOLTAGE") "16V") (field (name "BOM") "INCLUDE"))
      (libsource (lib "eagle-import") (part "C0805_IPCC-0.1U-16V-0805-X7R"))
    )
    (comp (ref "C104")
      (value "0.1uF")
      (footprint "eagle-import:0805_IPC-7351B")
      (fields (field (name "PACKAGE") "0805") (field (name "VOLTAGE") "16V") (field (name "BOM") "INCLUDE"))
      (libsource (lib "eagle-import") (part "C0805_IPCC-0.1U-16V-0805-X7R"))
    )
    (comp (ref "C105")
      (value "0.1uF")
      (footprint "eagle-import:0805_IPC-7351B")
      (fields (field (name "PACKAGE") "0805") (field (name "VOLTAGE") "16V") (field (name "BOM") "INCLUDE"))
      (libsource (lib "eagle-import") (part "C0805_IPCC-0.1U-16V-0805-X7R"))
    )
    (comp (ref "C106")
      (value "0.1uF")
      (footprint "eagle-import:0805_IPC-7351B")
      (fields (field (name "VOLTAGE") "16V"))
      (libsource (lib "eagle-import") (part "C0805_IPCC-0.1U-16V-0805-X7R"))
    )
    (comp (ref "C107")
      (value "0.1uF")
      (footprint "eagle-import:0805_IPC-7351B")
      (fields (field (name "VOLTAGE") "16V"))
      (libsource (lib "eagle-import") (part "C0805_IPCC-0.1U-16V-0805-X7R"))
    )
    (comp (ref "C109")
      (value "0.1uF")
      (footprint "eagle-import:0805_IPC-7351B")
      (fields (field (name "VOLTAGE") "16V"))
      (libsource (lib "eagle-import") (part "C0805_IPCC-0.1U-16V-0805-X7R"))
    )
    (comp (ref "C110")
      (value "0.1uF")
      (footprint "eagle-import:0805_IPC-7351B")
      (fields (field (name "VOLTAGE") "16V"))
      (libsource (lib "eagle-import") (part "C0805_IPCC-0.1U-16V-0805-X7R"))
    )
    (comp (ref "C111")
      (value "22nF")
      (footprint "eagle-import:C1206")
      (fields
        (field (name "BOM") "INCLUDE")
        (field (name "PACKAGE") "1206")
        (field (name "PARTNO") "C3216NP02E223J160AA")
        (field (name "VOLTAGE") "250V")
      )
      (libsource (lib "eagle-import") (part "CC1206C-22N-250V-5%-1206-NP0"))
    )
    (comp (ref "C112")
      (value "22nF")
      (footprint "eagle-import:C1206")
      (fields
        (field (name "BOM") "INCLUDE")
        (field (name "PACKAGE") "1206")
        (field (name "PARTNO") "C3216NP02E223J160AA")
        (field (name "VOLTAGE") "250V")
      )
      (libsource (lib "eagle-import") (part "CC1206C-22N-250V-5%-1206-NP0"))
    )
    (comp (ref "C113")
      (value "0.1uF")
      (footprint "eagle-import:0805_IPC-7351B")
      (fields (field (name "VOLTAGE") "16V"))
      (libsource (lib "eagle-import") (part "C0805_IPCC-0.1U-16V-0805-X7R"))
    )
    (comp (ref "C114")
      (value "0.1uF")
      (footprint "eagle-import:0805_IPC-7351B")
      (fields (field (name "VOLTAGE") "16V"))
      (libsource (lib "eagle-import") (part "C0805_IPCC-0.1U-16V-0805-X7R"))
    )
    (comp (ref "J101")
      (value "COAXBNC_EDGE")
      (footprint "eagle-import:BNC_EDGE")
      (libsource (lib "eagle-import") (part "COAXBNC_EDGE"))
    )
    (comp (ref "J102")
      (value "COAXBNC_EDGE")
      (footprint "eagle-import:BNC_EDGE")
      (libsource (lib "eagle-import") (part "COAXBNC_EDGE"))
    )
    (comp (ref "L6")
      (value "DR127")
      (footprint "eagle-import:DR127")
      (libsource (lib "eagle-import") (part "DR127"))
    )
    (comp (ref "L7")
      (value "DR127")
      (footprint "eagle-import:DR127")
      (libsource (lib "eagle-import") (part "DR127"))
    )
    (comp (ref "L101")
      (value "1uH")
      (footprint "eagle-import:L1008")
      (fields (field (name "PARTNO") "1008CS-102XJEC"))
      (libsource (lib "eagle-import") (part "L_CHIP1008L-1.0U-AIR-5%-1008-0.37A"))
    )
    (comp (ref "L102")
      (value "1uH")
      (footprint "eagle-import:L1008")
      (fields (field (name "PARTNO") "1008CS-102XJEC"))
      (libsource (lib "eagle-import") (part "L_CHIP1008L-1.0U-AIR-5%-1008-0.37A"))
    )
    (comp (ref "Q101")
      (value "IRF540")
      (footprint "eagle-import:TO220BV")
      (libsource (lib "eagle-import") (part "IRF540"))
    )
    (comp (ref "Q102")
      (value "IRF540")
      (footprint "eagle-import:TO220BV")
      (libsource (lib "eagle-import") (part "IRF540"))
    )
    (comp (ref "R30")
      (value "1.0K")
      (footprint "eagle-import:0805_IPC-7351B")
      (libsource (lib "eagle-import") (part "R0805_IPCR-1.0K-0.1%-0805-0.1W"))
    )
    (comp (ref "R31")
      (value "1.0K")
      (footprint "eagle-import:0805_IPC-7351B")
      (libsource (lib "eagle-import") (part "R0805_IPCR-1.0K-0.1%-0805-0.1W"))
    )
    (comp (ref "R32")
      (value "1K")
      (footprint "eagle-import:R2512")
      (fields (field (name "POWER") "1"))
      (libsource (lib "eagle-import") (part "RR2512R-1K-1%-2512-1W"))
    )
    (comp (ref "R33")
      (value "1K")
      (footprint "eagle-import:R2512")
      (fields (field (name "POWER") "1"))
      (libsource (lib "eagle-import") (part "RR2512R-1K-1%-2512-1W"))
    )
    (comp (ref "R34")
      (value "1K")
      (footprint "eagle-import:R2512")
      (fields (field (name "POWER") "1"))
      (libsource (lib "eagle-import") (part "RR2512R-1K-1%-2512-1W"))
    )
    (comp (ref "R35")
      (value "1K")
      (footprint "eagle-import:R2512")
      (fields (field (name "POWER") "1"))
      (libsource (lib "eagle-import") (part "RR2512R-1K-1%-2512-1W"))
    )
    (comp (ref "R101")
      (value "1K")
      (footprint "eagle-import:R1206")
      (fields (field (name "POWER") "0.25"))
      (libsource (lib "eagle-import") (part "RR1206R-1.0K-1%-1206-0.25W"))
    )
    (comp (ref "R102")
      (value "1K")
      (footprint "eagle-import:R1206")
      (fields (field (name "POWER") "0.25"))
      (libsource (lib "eagle-import") (part "RR1206R-1.0K-1%-1206-0.25W"))
    )
    (comp (ref "R103")
      (value "1K")
      (footprint "eagle-import:R1206")
      (fields (field (name "POWER") "0.25"))
      (libsource (lib "eagle-import") (part "RR1206R-1.0K-1%-1206-0.25W"))
    )
    (comp (ref "R104")
      (value "1K")
      (footprint "eagle-import:R1206")
      (fields (field (name "POWER") "0.25"))
      (libsource (lib "eagle-import") (part "RR1206R-1.0K-1%-1206-0.25W"))
    )
    (comp (ref "R105")
      (value "1K")
      (footprint "eagle-import:R1206")
      (fields (field (name "POWER") "0.25"))
      (libsource (lib "eagle-import") (part "RR1206R-1.0K-1%-1206-0.25W"))
    )
    (comp (ref "R106")
      (value "1K")
      (footprint "eagle-import:R1206")
      (fields (field (name "POWER") "0.25"))
      (libsource (lib "eagle-import") (part "RR1206R-1.0K-1%-1206-0.25W"))
    )
    (comp (ref "R107")
      (value "1.0K")
      (footprint "eagle-import:0805_IPC-7351B")
      (libsource (lib "eagle-import") (part "R0805_IPCR-1.0K-0.1%-0805-0.1W"))
    )
    (comp (ref "R108")
      (value "1K")
      (footprint "eagle-import:R1206")
      (fields (field (name "POWER") "0.25"))
      (libsource (lib "eagle-import") (part "RR1206R-1.0K-1%-1206-0.25W"))
    )
    (comp (ref "R109")
      (value "1.0K")
      (footprint "eagle-import:0805_IPC-7351B")
      (libsource (lib "eagle-import") (part "R0805_IPCR-1.0K-0.1%-0805-0.1W"))
    )
    (comp (ref "R110")
      (value "1K")
      (footprint "eagle-import:R1206")
      (fields (field (name "POWER") "0.25"))
      (libsource (lib "eagle-import") (part "RR1206R-1.0K-1%-1206-0.25W"))
    )
    (comp (ref "R111")
      (value "1.0K")
      (footprint "eagle-import:0805_IPC-7351B")
      (libsource (lib "eagle-import") (part "R0805_IPCR-1.0K-0.1%-0805-0.1W"))
    )
    (comp (ref "R112")
      (value "1.0K")
      (footprint "eagle-import:0805_IPC-7351B")
      (libsource (lib "eagle-import") (part "R0805_IPCR-1.0K-0.1%-0805-0.1W"))
    )
    (comp (ref "R113")
      (value "1.0K")
      (footprint "eagle-import:0805_IPC-7351B")
      (libsource (lib "eagle-import") (part "R0805_IPCR-1.0K-0.1%-0805-0.1W"))
    )
    (comp (ref "R114")
      (value "1.0K")
      (footprint "eagle-import:0805_IPC-7351B")
      (libsource (lib "eagle-import") (part "R0805_IPCR-1.0K-0.1%-0805-0.1W"))
    )
    (comp (ref "R115")
      (value "1.0K")
      (footprint "eagle-import:0805_IPC-7351B")
      (libsource (lib "eagle-import") (part "R0805_IPCR-1.0K-0.1%-0805-0.1W"))
    )
    (comp (ref "R116")
      (value "1.0K")
      (footprint "eagle-import:0805_IPC-7351B")
      (libsource (lib "eagle-import") (part "R0805_IPCR-1.0K-0.1%-0805-0.1W"))
    )
    (comp (ref "R117")
      (value "1K")
      (footprint "eagle-import:R2512")
      (fields (field (name "POWER") "1"))
      (libsource (lib "eagle-import") (part "RR2512R-1K-1%-2512-1W"))
    )
    (comp (ref "R118")
      (value "1K")
      (footprint "eagle-import:R2512")
      (fields (field (name "POWER") "1"))
      (libsource (lib "eagle-import") (part "RR2512R-1K-1%-2512-1W"))
    )
    (comp (ref "R119")
      (value "1K")
      (footprint "eagle-import:R2512")
      (fields (field (name "POWER") "1"))
      (libsource (lib "eagle-import") (part "RR2512R-1K-1%-2512-1W"))
    )
    (comp (ref "R120")
      (value "1K")
      (footprint "eagle-import:R2512")
      (fields (field (name "POWER") "1"))
      (libsource (lib "eagle-import") (part "RR2512R-1K-1%-2512-1W"))
    )
    (comp (ref "R121")
      (value "1K")
      (footprint "eagle-import:R2512")
      (fields (field (name "POWER") "1"))
      (libsource (lib "eagle-import") (part "RR2512R-1K-1%-2512-1W"))
    )
    (comp (ref "R122")
      (value "1K")
      (footprint "eagle-import:R2512")
      (fields (field (name "POWER") "1"))
      (libsource (lib "eagle-import") (part "RR2512R-1K-1%-2512-1W"))
    )
    (comp (ref "R123")
      (value "1K")
      (footprint "eagle-import:R2512")
      (fields (field (name "POWER") "1"))
      (libsource (lib "eagle-import") (part "RR2512R-1K-1%-2512-1W"))
    )
    (comp (ref "R124")
      (value "1K")
      (footprint "eagle-import:R2512")
      (fields (field (name "POWER") "1"))
      (libsource (lib "eagle-import") (part "RR2512R-1K-1%-2512-1W"))
    )
    (comp (ref "R125")
      (value "1.0K")
      (footprint "eagle-import:0805_IPC-7351B")
      (libsource (lib "eagle-import") (part "R0805_IPCR-1.0K-0.1%-0805-0.1W"))
    )
    (comp (ref "R126")
      (value "1.0K")
      (footprint "eagle-import:0805_IPC-7351B")
      (libsource (lib "eagle-import") (part "R0805_IPCR-1.0K-0.1%-0805-0.1W"))
    )
    (comp (ref "T1")
      (value "HP4_TRAFO")
      (footprint "eagle-import:HP4")
      (libsource (lib "eagle-import") (part "HP4_TRAFO"))
    )
    (comp (ref "T2")
      (value "HP4_TRAFO")
      (footprint "eagle-import:HP4")
      (libsource (lib "eagle-import") (part "HP4_TRAFO"))
    )
    (comp (ref "TP1")
      (value "PROBE_TPTP_5MM")
      (footprint "eagle-import:PROBE_TP_5MM")
      (libsource (lib "eagle-import") (part "PROBE_TPTP_5MM"))
    )
    (comp (ref "TP2")
      (value "PROBE_TPTP_7P5MM")
      (footprint "eagle-import:PROBE_TP_7P5MM")
      (libsource (lib "eagle-import") (part "PROBE_TPTP_7P5MM"))
    )
    (comp (ref "TP3")
      (value "PROBE_TPTP_5MM")
      (footprint "eagle-import:PROBE_TP_5MM")
      (libsource (lib "eagle-import") (part "PROBE_TPTP_5MM"))
    )
    (comp (ref "TP4")
      (value "PROBE_TPTP_7P5MM")
      (footprint "eagle-import:PROBE_TP_7P5MM")
      (libsource (lib "eagle-import") (part "PROBE_TPTP_7P5MM"))
    )
    (comp (ref "TP5")
      (value "PROBE_TPTP_7P5MM")
      (footprint "eagle-import:PROBE_TP_7P5MM")
      (libsource (lib "eagle-import") (part "PROBE_TPTP_7P5MM"))
    )
    (comp (ref "TP6")
      (value "PROBE_TPTP_7P5MM")
      (footprint "eagle-import:PROBE_TP_7P5MM")
      (libsource (lib "eagle-import") (part "PROBE_TPTP_7P5MM"))
    )
    (comp (ref "TP14")
      (value "PROBE_TPTP_5MM")
      (footprint "eagle-import:PROBE_TP_5MM")
      (libsource (lib "eagle-import") (part "PROBE_TPTP_5MM"))
    )
    (comp (ref "TP15")
      (value "PROBE_TPTP_5MM")
      (footprint "eagle-import:PROBE_TP_5MM")
      (libsource (lib "eagle-import") (part "PROBE_TPTP_5MM"))
    )
    (comp (ref "TP18")
      (value "PROBE_TPTP_5MM")
      (footprint "eagle-import:PROBE_TP_5MM")
      (libsource (lib "eagle-import") (part "PROBE_TPTP_5MM"))
    )
    (comp (ref "TP19")
      (value "PROBE_TPTP_5MM")
      (footprint "eagle-import:PROBE_TP_5MM")
      (libsource (lib "eagle-import") (part "PROBE_TPTP_5MM"))
    )
  )
  (nets
    (net (code "1") (name "+5V") (class "Default")
      (node (ref "C14") (pin "+") (pinfunction "+_+") (pintype "passive"))
      (node (ref "C16") (pin "1") (pinfunction "1_1") (pintype "passive"))
      (node (ref "C22") (pin "1") (pinfunction "1_1") (pintype "passive"))
      (node (ref "IC201") (pin "5") (pinfunction "VCC_5") (pintype "power_in"))
      (node (ref "IC302") (pin "OUT") (pinfunction "OUT_OUT") (pintype "passive"))
      (node (ref "LED1") (pin "A") (pinfunction "A_A") (pintype "passive"))
      (node (ref "LED3") (pin "A") (pinfunction "A_A") (pintype "passive"))
      (node (ref "R201") (pin "3") (pinfunction "E_3") (pintype "passive"))
      (node (ref "R29") (pin "1") (pinfunction "1_1") (pintype "passive"))
    )
    (net (code "2") (name "+12V") (class "Default")
      (node (ref "C15") (pin "1") (pinfunction "1_1") (pintype "passive"))
      (node (ref "C210") (pin "1") (pinfunction "1_1") (pintype "passive"))
      (node (ref "C31") (pin "+") (pinfunction "+_+") (pintype "passive"))
      (node (ref "IC202") (pin "4") (pinfunction "V+_4") (pintype "power_in"))
      (node (ref "IC301") (pin "OUT") (pinfunction "OUT_OUT") (pintype "passive"))
      (node (ref "J2") (pin "2") (pinfunction "2_2") (pintype "passive"))
      (node (ref "LED2") (pin "A") (pinfunction "A_A") (pintype "passive"))
      (node (ref "T201") (pin "C") (pinfunction "C_C") (pintype "passive"))
    )
    (net (code "3") (name "ABN1") (class "Default")
      (node (ref "R101") (pin "1") (pinfunction "1_1") (pintype "passive"))
      (node (ref "R103") (pin "1") (pinfunction "1_1") (pintype "passive"))
      (node (ref "R13") (pin "1") (pinfunction "1_1") (pintype "passive"))
      (node (ref "R6") (pin "1") (pinfunction "1_1") (pintype "passive"))
      (node (ref "T1") (pin "11") (pinfunction "F2_11") (pintype "passive"))
      (node (ref "TP18") (pin "TP") (pinfunction "1_TP") (pintype "passive"))
    )
    (net (code "4") (name "ABP1") (class "Default")
      (node (ref "R102") (pin "1") (pinfunction "1_1") (pintype "passive"))
      (node (ref "R104") (pin "1") (pinfunction "1_1") (pintype "passive"))
      (node (ref "R19") (pin "1") (pinfunction "1_1") (pintype "passive"))
      (node (ref "R26") (pin "1") (pinfunction "1_1") (pintype "passive"))
      (node (ref "T1") (pin "1") (pinfunction "S1_1") (pintype "passive"))
      (node (ref "TP19") (pin "TP") (pinfunction "1_TP") (pintype "passive"))
    )
    (net (code "5") (name "AN2") (class "Default")
      (node (ref "C103") (pin "2") (pinfunction "2_2") (pintype "passive"))
      (node (ref "R103") (pin "2") (pinfunction "2_2") (pintype "passive"))
      (node (ref "R105") (pin "1") (pinfunction "1_1") (pintype "passive"))
    )
    (net (code "6") (name "AN3") (class "Default")
      (node (ref "C103") (pin "1") (pinfunction "1_1") (pintype "passive"))
      (node (ref "L101") (pin "1") (pinfunction "1_1") (pintype "passive"))
      (node (ref "R108") (pin "2") (pinfunction "2_2") (pintype "passive"))
      (node (ref "R111") (pin "1") (pinfunction "1_1") (pintype "passive"))
      (node (ref "R113") (pin "1") (pinfunction "1_1") (pintype "passive"))
    )
    (net (code "7") (name "AN4") (class "Default")
      (node (ref "L101") (pin "2") (pinfunction "2_2") (pintype "passive"))
      (node (ref "Q101") (pin "G") (pinfunction "G_G") (pintype "passive"))
      (node (ref "R113") (pin "2") (pinfunction "2_2") (pintype "passive"))
      (node (ref "R115") (pin "1") (pinfunction "1_1") (pintype "passive"))
      (node (ref "R117") (pin "1") (pinfunction "1_1") (pintype "passive"))
      (node (ref "R118") (pin "1") (pinfunction "1_1") (pintype "passive"))
      (node (ref "TP3") (pin "TP") (pinfunction "1_TP") (pintype "passive"))
    )
    (net (code "8") (name "AN5") (class "Default")
      (node (ref "Q101") (pin "S") (pinfunction "S_S") (pintype "passive"))
      (node (ref "R121") (pin "1") (pinfunction "1_1") (pintype "passive"))
      (node (ref "R123") (pin "1") (pinfunction "1_1") (pintype "passive"))
      (node (ref "R125") (pin "1") (pinfunction "1_1") (pintype "passive"))
      (node (ref "R34") (pin "1") (pinfunction "1_1") (pintype "passive"))
      (node (ref "R35") (pin "1") (pinfunction "1_1") (pintype "passive"))
      (node (ref "TP6") (pin "TP") (pinfunction "1_TP") (pintype "passive"))
    )
    (net (code "9") (name "AN6") (class "Default")
      (node (ref "C113") (pin "1") (pinfunction "1_1") (pintype "passive"))
      (node (ref "R125") (pin "2") (pinfunction "2_2") (pintype "passive"))
      (node (ref "TP15") (pin "TP") (pinfunction "1_TP") (pintype "passive"))
    )
    (net (code "10") (name "AP2") (class "Default")
      (node (ref "C105") (pin "2") (pinfunction "2_2") (pintype "passive"))
      (node (ref "R104") (pin "2") (pinfunction "2_2") (pintype "passive"))
      (node (ref "R106") (pin "1") (pinfunction "1_1") (pintype "passive"))
    )
    (net (code "11") (name "AP3") (class "Default")
      (node (ref "C105") (pin "1") (pinfunction "1_1") (pintype "passive"))
      (node (ref "L102") (pin "1") (pinfunction "1_1") (pintype "passive"))
      (node (ref "R110") (pin "2") (pinfunction "2_2") (pintype "passive"))
      (node (ref "R112") (pin "1") (pinfunction "1_1") (pintype "passive"))
      (node (ref "R114") (pin "1") (pinfunction "1_1") (pintype "passive"))
    )
    (net (code "12") (name "AP4") (class "Default")
      (node (ref "L102") (pin "2") (pinfunction "2_2") (pintype "passive"))
      (node (ref "Q102") (pin "G") (pinfunction "G_G") (pintype "passive"))
      (node (ref "R114") (pin "2") (pinfunction "2_2") (pintype "passive"))
      (node (ref "R116") (pin "1") (pinfunction "1_1") (pintype "passive"))
      (node (ref "R119") (pin "1") (pinfunction "1_1") (pintype "passive"))
      (node (ref "R120") (pin "1") (pinfunction "1_1") (pintype "passive"))
      (node (ref "TP1") (pin "TP") (pinfunction "1_TP") (pintype "passive"))
    )
    (net (code "13") (name "AP5") (class "Default")
      (node (ref "Q102") (pin "S") (pinfunction "S_S") (pintype "passive"))
      (node (ref "R122") (pin "1") (pinfunction "1_1") (pintype "passive"))
      (node (ref "R124") (pin "1") (pinfunction "1_1") (pintype "passive"))
      (node (ref "R126") (pin "1") (pinfunction "1_1") (pintype "passive"))
      (node (ref "R32") (pin "1") (pinfunction "1_1") (pintype "passive"))
      (node (ref "R33") (pin "1") (pinfunction "1_1") (pintype "passive"))
      (node (ref "TP5") (pin "TP") (pinfunction "1_TP") (pintype "passive"))
    )
    (net (code "14") (name "AP6") (class "Default")
      (node (ref "C114") (pin "1") (pinfunction "1_1") (pintype "passive"))
      (node (ref "R126") (pin "2") (pinfunction "2_2") (pintype "passive"))
      (node (ref "TP14") (pin "TP") (pinfunction "1_TP") (pintype "passive"))
    )
    (net (code "15") (name "BN2") (class "Default")
      (node (ref "C5") (pin "2") (pinfunction "2_2") (pintype "passive"))
      (node (ref "R5") (pin "1") (pinfunction "1_1") (pintype "passive"))
      (node (ref "R6") (pin "2") (pinfunction "2_2") (pintype "passive"))
    )
    (net (code "16") (name "BN3") (class "Default")
      (node (ref "C5") (pin "1") (pinfunction "1_1") (pintype "passive"))
      (node (ref "L1") (pin "1") (pinfunction "1_1") (pintype "passive"))
      (node (ref "R4") (pin "2") (pinfunction "2_2") (pintype "passive"))
      (node (ref "R8") (pin "1") (pinfunction "1_1") (pintype "passive"))
      (node (ref "R9") (pin "1") (pinfunction "1_1") (pintype "passive"))
    )
    (net (code "17") (name "BN4") (class "Default")
      (node (ref "L1") (pin "2") (pinfunction "2_2") (pintype "passive"))
      (node (ref "Q2") (pin "G") (pinfunction "G_G") (pintype "passive"))
      (node (ref "R1") (pin "1") (pinfunction "1_1") (pintype "passive"))
      (node (ref "R10") (pin "1") (pinfunction "1_1") (pintype "passive"))
      (node (ref "R7") (pin "1") (pinfunction "1_1") (pintype "passive"))
      (node (ref "R8") (pin "2") (pinfunction "2_2") (pintype "passive"))
      (node (ref "TP9") (pin "TP") (pinfunction "1_TP") (pintype "passive"))
    )
    (net (code "18") (name "BN5") (class "Default")
      (node (ref "Q2") (pin "S") (pinfunction "S_S") (pintype "passive"))
      (node (ref "R11") (pin "1") (pinfunction "1_1") (pintype "passive"))
      (node (ref "R2") (pin "1") (pinfunction "1_1") (pintype "passive"))
      (node (ref "R3") (pin "1") (pinfunction "1_1") (pintype "passive"))
      (node (ref "R36") (pin "1") (pinfunction "1_1") (pintype "passive"))
      (node (ref "R37") (pin "1") (pinfunction "1_1") (pintype "passive"))
      (node (ref "TP10") (pin "TP") (pinfunction "1_TP") (pintype "passive"))
    )
    (net (code "19") (name "BN6") (class "Default")
      (node (ref "C2") (pin "1") (pinfunction "1_1") (pintype "passive"))
      (node (ref "R11") (pin "2") (pinfunction "2_2") (pintype "passive"))
      (node (ref "TP17") (pin "TP") (pinfunction "1_TP") (pintype "passive"))
    )
    (net (code "20") (name "BP2") (class "Default")
      (node (ref "C11") (pin "2") (pinfunction "2_2") (pintype "passive"))
      (node (ref "R18") (pin "1") (pinfunction "1_1") (pintype "passive"))
      (node (ref "R19") (pin "2") (pinfunction "2_2") (pintype "passive"))
    )
    (net (code "21") (name "BP3") (class "Default")
      (node (ref "C11") (pin "1") (pinfunction "1_1") (pintype "passive"))
      (node (ref "L2") (pin "1") (pinfunction "1_1") (pintype "passive"))
      (node (ref "R17") (pin "2") (pinfunction "2_2") (pintype "passive"))
      (node (ref "R21") (pin "1") (pinfunction "1_1") (pintype "passive"))
      (node (ref "R22") (pin "1") (pinfunction "1_1") (pintype "passive"))
    )
    (net (code "22") (name "BP4") (class "Default")
      (node (ref "L2") (pin "2") (pinfunction "2_2") (pintype "passive"))
      (node (ref "Q1") (pin "G") (pinfunction "G_G") (pintype "passive"))
      (node (ref "R14") (pin "1") (pinfunction "1_1") (pintype "passive"))
      (node (ref "R20") (pin "1") (pinfunction "1_1") (pintype "passive"))
      (node (ref "R21") (pin "2") (pinfunction "2_2") (pintype "passive"))
      (node (ref "R23") (pin "1") (pinfunction "1_1") (pintype "passive"))
      (node (ref "TP7") (pin "TP") (pinfunction "1_TP") (pintype "passive"))
    )
    (net (code "23") (name "BP5") (class "Default")
      (node (ref "Q1") (pin "S") (pinfunction "S_S") (pintype "passive"))
      (node (ref "R15") (pin "1") (pinfunction "1_1") (pintype "passive"))
      (node (ref "R16") (pin "1") (pinfunction "1_1") (pintype "passive"))
      (node (ref "R24") (pin "1") (pinfunction "1_1") (pintype "passive"))
      (node (ref "R38") (pin "1") (pinfunction "1_1") (pintype "passive"))
      (node (ref "R39") (pin "1") (pinfunction "1_1") (pintype "passive"))
      (node (ref "TP8") (pin "TP") (pinfunction "1_TP") (pintype "passive"))
    )
    (net (code "24") (name "BP6") (class "Default")
      (node (ref "C8") (pin "1") (pinfunction "1_1") (pintype "passive"))
      (node (ref "R24") (pin "2") (pinfunction "2_2") (pintype "passive"))
      (node (ref "TP16") (pin "TP") (pinfunction "1_TP") (pintype "passive"))
    )
    (net (code "25") (name "DRAINS_NEG") (class "Default")
      (node (ref "C1") (pin "2") (pinfunction "2_2") (pintype "passive"))
      (node (ref "C111") (pin "2") (pinfunction "2_2") (pintype "passive"))
      (node (ref "C18") (pin "2") (pinfunction "2_2") (pintype "passive"))
      (node (ref "L7") (pin "1") (pinfunction "1_1") (pintype "passive"))
      (node (ref "Q101") (pin "D") (pinfunction "D_D") (pintype "passive"))
      (node (ref "Q2") (pin "D") (pinfunction "D_D") (pintype "passive"))
      (node (ref "T2") (pin "8") (pinfunction "F5_8") (pintype "passive"))
      (node (ref "TP4") (pin "TP") (pinfunction "1_TP") (pintype "passive"))
    )
    (net (code "26") (name "DRAINS_POS") (class "Default")
      (node (ref "C112") (pin "2") (pinfunction "2_2") (pintype "passive"))
      (node (ref "C17") (pin "2") (pinfunction "2_2") (pintype "passive"))
      (node (ref "C7") (pin "2") (pinfunction "2_2") (pintype "passive"))
      (node (ref "L6") (pin "1") (pinfunction "1_1") (pintype "passive"))
      (node (ref "Q1") (pin "D") (pinfunction "D_D") (pintype "passive"))
      (node (ref "Q102") (pin "D") (pinfunction "D_D") (pintype "passive"))
      (node (ref "T2") (pin "6") (pinfunction "S6_6") (pintype "passive"))
      (node (ref "TP2") (pin "TP") (pinfunction "1_TP") (pintype "passive"))
    )
    (net (code "27") (name "GBIAS") (class "Default")
      (node (ref "R107") (pin "1") (pinfunction "1_1") (pintype "passive"))
      (node (ref "R109") (pin "1") (pinfunction "1_1") (pintype "passive"))
      (node (ref "R12") (pin "1") (pinfunction "1_1") (pintype "passive"))
      (node (ref "R218") (pin "2") (pinfunction "2_2") (pintype "passive"))
      (node (ref "R219") (pin "2") (pinfunction "2_2") (pintype "passive"))
      (node (ref "R25") (pin "1") (pinfunction "1_1") (pintype "passive"))
      (node (ref "T201") (pin "E") (pinfunction "E_E") (pintype "passive"))
      (node (ref "T202") (pin "E") (pinfunction "E_E") (pintype "passive"))
      (node (ref "TP11") (pin "TP") (pinfunction "1_TP") (pintype "passive"))
    )
    (net (code "28") (name "GND") (class "Default")
      (node (ref "C10") (pin "2") (pinfunction "2_2") (pintype "passive"))
      (node (ref "C102") (pin "2") (pinfunction "2_2") (pintype "passive"))
      (node (ref "C104") (pin "2") (pinfunction "2_2") (pintype "passive"))
      (node (ref "C106") (pin "2") (pinfunction "2_2") (pintype "passive"))
      (node (ref "C107") (pin "2") (pinfunction "2_2") (pintype "passive"))
      (node (ref "C109") (pin "2") (pinfunction "2_2") (pintype "passive"))
      (node (ref "C110") (pin "2") (pinfunction "2_2") (pintype "passive"))
      (node (ref "C113") (pin "2") (pinfunction "2_2") (pintype "passive"))
      (node (ref "C114") (pin "2") (pinfunction "2_2") (pintype "passive"))
      (node (ref "C12") (pin "2") (pinfunction "2_2") (pintype "passive"))
      (node (ref "C13") (pin "2") (pinfunction "2_2") (pintype "passive"))
      (node (ref "C14") (pin "-") (pinfunction "-_-") (pintype "passive"))
      (node (ref "C15") (pin "2") (pinfunction "2_2") (pintype "passive"))
      (node (ref "C16") (pin "2") (pinfunction "2_2") (pintype "passive"))
      (node (ref "C19") (pin "2") (pinfunction "2_2") (pintype "passive"))
      (node (ref "C2") (pin "2") (pinfunction "2_2") (pintype "passive"))
      (node (ref "C20") (pin "2") (pinfunction "2_2") (pintype "passive"))
      (node (ref "C201") (pin "2") (pinfunction "2_2") (pintype "passive"))
      (node (ref "C207") (pin "2") (pinfunction "2_2") (pintype "passive"))
      (node (ref "C208") (pin "2") (pinfunction "2_2") (pintype "passive"))
      (node (ref "C21") (pin "2") (pinfunction "2_2") (pintype "passive"))
      (node (ref "C210") (pin "2") (pinfunction "2_2") (pintype "passive"))
      (node (ref "C22") (pin "2") (pinfunction "2_2") (pintype "passive"))
      (node (ref "C23") (pin "2") (pinfunction "2_2") (pintype "passive"))
      (node (ref "C3") (pin "2") (pinfunction "2_2") (pintype "passive"))
      (node (ref "C30") (pin "2") (pinfunction "2_2") (pintype "passive"))
      (node (ref "C301") (pin "-") (pinfunction "-_-") (pintype "passive"))
      (node (ref "C303") (pin "2") (pinfunction "2_2") (pintype "passive"))
      (node (ref "C304") (pin "2") (pinfunction "2_2") (pintype "passive"))
      (node (ref "C31") (pin "-") (pinfunction "-_-") (pintype "passive"))
      (node (ref "C4") (pin "2") (pinfunction "2_2") (pintype "passive"))
      (node (ref "C6") (pin "2") (pinfunction "2_2") (pintype "passive"))
      (node (ref "C8") (pin "2") (pinfunction "2_2") (pintype "passive"))
      (node (ref "C9") (pin "2") (pinfunction "2_2") (pintype "passive"))
      (node (ref "D301") (pin "A") (pinfunction "A_A") (pintype "passive"))
      (node (ref "H1") (pin "B3,2") (pinfunction "MOUNT_B3,2") (pintype "passive"))
      (node (ref "H2") (pin "B3,2") (pinfunction "MOUNT_B3,2") (pintype "passive"))
      (node (ref "H3") (pin "B3,2") (pinfunction "MOUNT_B3,2") (pintype "passive"))
      (node (ref "H4") (pin "B3,2") (pinfunction "MOUNT_B3,2") (pintype "passive"))
      (node (ref "IC201") (pin "3") (pinfunction "GND_3") (pintype "power_in"))
      (node (ref "IC202") (pin "11") (pinfunction "V-_11") (pintype "power_in"))
      (node (ref "IC301") (pin "GND") (pinfunction "GND_GND") (pintype "input"))
      (node (ref "IC302") (pin "GND") (pinfunction "GND_GND") (pintype "input"))
      (node (ref "J101") (pin "G1") (pinfunction "GND1_G1") (pintype "power_in"))
      (node (ref "J101") (pin "G2") (pinfunction "GND1_G2") (pintype "power_in"))
      (node (ref "J101") (pin "G3") (pinfunction "GND1_G3") (pintype "power_in"))
      (node (ref "J101") (pin "G4") (pinfunction "GND1_G4") (pintype "power_in"))
      (node (ref "J102") (pin "G1") (pinfunction "GND1_G1") (pintype "power_in"))
      (node (ref "J102") (pin "G2") (pinfunction "GND1_G2") (pintype "power_in"))
      (node (ref "J102") (pin "G3") (pinfunction "GND1_G3") (pintype "power_in"))
      (node (ref "J102") (pin "G4") (pinfunction "GND1_G4") (pintype "power_in"))
      (node (ref "J2") (pin "1") (pinfunction "1_1") (pintype "passive"))
      (node (ref "J202") (pin "G1") (pinfunction "GND1_G1") (pintype "power_in"))
      (node (ref "J202") (pin "G2") (pinfunction "GND1_G2") (pintype "power_in"))
      (node (ref "J202") (pin "G3") (pinfunction "GND1_G3") (pintype "power_in"))
      (node (ref "J202") (pin "G4") (pinfunction "GND1_G4") (pintype "power_in"))
      (node (ref "Q201") (pin "2") (pinfunction "S_2") (pintype "passive"))
      (node (ref "R101") (pin "2") (pinfunction "2_2") (pintype "passive"))
      (node (ref "R102") (pin "2") (pinfunction "2_2") (pintype "passive"))
      (node (ref "R105") (pin "2") (pinfunction "2_2") (pintype "passive"))
      (node (ref "R106") (pin "2") (pinfunction "2_2") (pintype "passive"))
      (node (ref "R121") (pin "2") (pinfunction "2_2") (pintype "passive"))
      (node (ref "R122") (pin "2") (pinfunction "2_2") (pintype "passive"))
      (node (ref "R123") (pin "2") (pinfunction "2_2") (pintype "passive"))
      (node (ref "R124") (pin "2") (pinfunction "2_2") (pintype "passive"))
      (node (ref "R13") (pin "2") (pinfunction "2_2") (pintype "passive"))
      (node (ref "R15") (pin "2") (pinfunction "2_2") (pintype "passive"))
      (node (ref "R16") (pin "2") (pinfunction "2_2") (pintype "passive"))
      (node (ref "R18") (pin "2") (pinfunction "2_2") (pintype "passive"))
      (node (ref "R2") (pin "2") (pinfunction "2_2") (pintype "passive"))
      (node (ref "R201") (pin "1") (pinfunction "A_1") (pintype "passive"))
      (node (ref "R204") (pin "2") (pinfunction "2_2") (pintype "passive"))
      (node (ref "R211") (pin "2") (pinfunction "2_2") (pintype "passive"))
      (node (ref "R212") (pin "1") (pinfunction "1_1") (pintype "passive"))
      (node (ref "R26") (pin "2") (pinfunction "2_2") (pintype "passive"))
      (node (ref "R27") (pin "2") (pinfunction "2_2") (pintype "passive"))
      (node (ref "R28") (pin "2") (pinfunction "2_2") (pintype "passive"))
      (node (ref "R3") (pin "2") (pinfunction "2_2") (pintype "passive"))
      (node (ref "R31") (pin "2") (pinfunction "2_2") (pintype "passive"))
      (node (ref "R32") (pin "2") (pinfunction "2_2") (pintype "passive"))
      (node (ref "R33") (pin "2") (pinfunction "2_2") (pintype "passive"))
      (node (ref "R34") (pin "2") (pinfunction "2_2") (pintype "passive"))
      (node (ref "R35") (pin "2") (pinfunction "2_2") (pintype "passive"))
      (node (ref "R36") (pin "2") (pinfunction "2_2") (pintype "passive"))
      (node (ref "R37") (pin "2") (pinfunction "2_2") (pintype "passive"))
      (node (ref "R38") (pin "2") (pinfunction "2_2") (pintype "passive"))
      (node (ref "R39") (pin "2") (pinfunction "2_2") (pintype "passive"))
      (node (ref "R5") (pin "2") (pinfunction "2_2") (pintype "passive"))
      (node (ref "T1") (pin "10") (pinfunction "F3_10") (pintype "passive"))
      (node (ref "T2") (pin "9") (pinfunction "F4_9") (pintype "passive"))
      (node (ref "T202") (pin "C") (pinfunction "C_C") (pintype "passive"))
      (node (ref "TP1") (pin "GND") (pinfunction "GND1_GND") (pintype "power_in"))
      (node (ref "TP10") (pin "GND") (pinfunction "GND1_GND") (pintype "power_in"))
      (node (ref "TP11") (pin "GND") (pinfunction "GND1_GND") (pintype "power_in"))
      (node (ref "TP12") (pin "GND") (pinfunction "GND1_GND") (pintype "power_in"))
      (node (ref "TP13") (pin "GND") (pinfunction "GND1_GND") (pintype "power_in"))
      (node (ref "TP14") (pin "GND") (pinfunction "GND1_GND") (pintype "power_in"))
      (node (ref "TP15") (pin "GND") (pinfunction "GND1_GND") (pintype "power_in"))
      (node (ref "TP16") (pin "GND") (pinfunction "GND1_GND") (pintype "power_in"))
      (node (ref "TP17") (pin "GND") (pinfunction "GND1_GND") (pintype "power_in"))
      (node (ref "TP18") (pin "GND") (pinfunction "GND1_GND") (pintype "power_in"))
      (node (ref "TP19") (pin "GND") (pinfunction "GND1_GND") (pintype "power_in"))
      (node (ref "TP2") (pin "GND") (pinfunction "GND1_GND") (pintype "power_in"))
      (node (ref "TP3") (pin "GND") (pinfunction "GND1_GND") (pintype "power_in"))
      (node (ref "TP4") (pin "GND") (pinfunction "GND1_GND") (pintype "power_in"))
      (node (ref "TP5") (pin "GND") (pinfunction "GND1_GND") (pintype "power_in"))
      (node (ref "TP6") (pin "GND") (pinfunction "GND1_GND") (pintype "power_in"))
      (node (ref "TP7") (pin "GND") (pinfunction "GND1_GND") (pintype "power_in"))
      (node (ref "TP8") (pin "GND") (pinfunction "GND1_GND") (pintype "power_in"))
      (node (ref "TP9") (pin "GND") (pinfunction "GND1_GND") (pintype "power_in"))
      (node (ref "X1") (pin "2") (pinfunction "KL_2") (pintype "passive"))
      (node (ref "X101") (pin "P1") (pinfunction "P$1_P1") (pintype "bidirectional"))
      (node (ref "X101") (pin "P2") (pinfunction "P$2_P2") (pintype "bidirectional"))
    )
    (net (code "29") (name "Net-(C1-Pad1)") (class "Default")
      (node (ref "C1") (pin "1") (pinfunction "1_1") (pintype "passive"))
      (node (ref "R1") (pin "2") (pinfunction "2_2") (pintype "passive"))
      (node (ref "R7") (pin "2") (pinfunction "2_2") (pintype "passive"))
    )
    (net (code "30") (name "Net-(C3-Pad1)") (class "Default")
      (node (ref "C3") (pin "1") (pinfunction "1_1") (pintype "passive"))
      (node (ref "R10") (pin "2") (pinfunction "2_2") (pintype "passive"))
    )
    (net (code "31") (name "Net-(C4-Pad1)") (class "Default")
      (node (ref "C4") (pin "1") (pinfunction "1_1") (pintype "passive"))
      (node (ref "R9") (pin "2") (pinfunction "2_2") (pintype "passive"))
    )
    (net (code "32") (name "Net-(C6-Pad1)") (class "Default")
      (node (ref "C6") (pin "1") (pinfunction "1_1") (pintype "passive"))
      (node (ref "R12") (pin "2") (pinfunction "2_2") (pintype "passive"))
      (node (ref "R4") (pin "1") (pinfunction "1_1") (pintype "passive"))
    )
    (net (code "33") (name "Net-(C7-Pad1)") (class "Default")
      (node (ref "C7") (pin "1") (pinfunction "1_1") (pintype "passive"))
      (node (ref "R14") (pin "2") (pinfunction "2_2") (pintype "passive"))
      (node (ref "R20") (pin "2") (pinfunction "2_2") (pintype "passive"))
    )
    (net (code "34") (name "Net-(C9-Pad1)") (class "Default")
      (node (ref "C9") (pin "1") (pinfunction "1_1") (pintype "passive"))
      (node (ref "R23") (pin "2") (pinfunction "2_2") (pintype "passive"))
    )
    (net (code "35") (name "Net-(C10-Pad1)") (class "Default")
      (node (ref "C10") (pin "1") (pinfunction "1_1") (pintype "passive"))
      (node (ref "R22") (pin "2") (pinfunction "2_2") (pintype "passive"))
    )
    (net (code "36") (name "Net-(C12-Pad1)") (class "Default")
      (node (ref "C12") (pin "1") (pinfunction "1_1") (pintype "passive"))
      (node (ref "R17") (pin "1") (pinfunction "1_1") (pintype "passive"))
      (node (ref "R25") (pin "2") (pinfunction "2_2") (pintype "passive"))
    )
    (net (code "37") (name "Net-(C13-Pad1)") (class "Default")
      (node (ref "C13") (pin "1") (pinfunction "1_1") (pintype "passive"))
      (node (ref "IC301") (pin "IN") (pinfunction "IN_IN") (pintype "input"))
      (node (ref "R302") (pin "2") (pinfunction "2_2") (pintype "passive"))
    )
    (net (code "38") (name "Net-(C23-Pad1)") (class "Default")
      (node (ref "C23") (pin "1") (pinfunction "1_1") (pintype "passive"))
      (node (ref "C301") (pin "+") (pinfunction "+_+") (pintype "passive"))
      (node (ref "D2") (pin "C") (pinfunction "C_C") (pintype "passive"))
      (node (ref "L4") (pin "1") (pinfunction "1_1") (pintype "passive"))
      (node (ref "R301") (pin "2") (pinfunction "2_2") (pintype "passive"))
    )
    (net (code "39") (name "Net-(C30-Pad1)") (class "Default")
      (node (ref "C30") (pin "1") (pinfunction "1_1") (pintype "passive"))
      (node (ref "IC302") (pin "IN") (pinfunction "IN_IN") (pintype "input"))
      (node (ref "R303") (pin "2") (pinfunction "2_2") (pintype "passive"))
    )
    (net (code "40") (name "Net-(C102-Pad1)") (class "Default")
      (node (ref "C102") (pin "1") (pinfunction "1_1") (pintype "passive"))
      (node (ref "R107") (pin "2") (pinfunction "2_2") (pintype "passive"))
      (node (ref "R108") (pin "1") (pinfunction "1_1") (pintype "passive"))
    )
    (net (code "41") (name "Net-(C104-Pad1)") (class "Default")
      (node (ref "C104") (pin "1") (pinfunction "1_1") (pintype "passive"))
      (node (ref "R109") (pin "2") (pinfunction "2_2") (pintype "passive"))
      (node (ref "R110") (pin "1") (pinfunction "1_1") (pintype "passive"))
    )
    (net (code "42") (name "Net-(C106-Pad1)") (class "Default")
      (node (ref "C106") (pin "1") (pinfunction "1_1") (pintype "passive"))
      (node (ref "R111") (pin "2") (pinfunction "2_2") (pintype "passive"))
    )
    (net (code "43") (name "Net-(C107-Pad1)") (class "Default")
      (node (ref "C107") (pin "1") (pinfunction "1_1") (pintype "passive"))
      (node (ref "R112") (pin "2") (pinfunction "2_2") (pintype "passive"))
    )
    (net (code "44") (name "Net-(C109-Pad1)") (class "Default")
      (node (ref "C109") (pin "1") (pinfunction "1_1") (pintype "passive"))
      (node (ref "R115") (pin "2") (pinfunction "2_2") (pintype "passive"))
    )
    (net (code "45") (name "Net-(C110-Pad1)") (class "Default")
      (node (ref "C110") (pin "1") (pinfunction "1_1") (pintype "passive"))
      (node (ref "R116") (pin "2") (pinfunction "2_2") (pintype "passive"))
    )
    (net (code "46") (name "Net-(C111-Pad1)") (class "Default")
      (node (ref "C111") (pin "1") (pinfunction "1_1") (pintype "passive"))
      (node (ref "R117") (pin "2") (pinfunction "2_2") (pintype "passive"))
      (node (ref "R118") (pin "2") (pinfunction "2_2") (pintype "passive"))
    )
    (net (code "47") (name "Net-(C112-Pad1)") (class "Default")
      (node (ref "C112") (pin "1") (pinfunction "1_1") (pintype "passive"))
      (node (ref "R119") (pin "2") (pinfunction "2_2") (pintype "passive"))
      (node (ref "R120") (pin "2") (pinfunction "2_2") (pintype "passive"))
    )
    (net (code "48") (name "Net-(C207-Pad1)") (class "Default")
      (node (ref "C207") (pin "1") (pinfunction "1_1") (pintype "passive"))
      (node (ref "R214") (pin "1") (pinfunction "1_1") (pintype "passive"))
    )
    (net (code "49") (name "Net-(C209-Pad1)") (class "Default")
      (node (ref "C209") (pin "1") (pinfunction "1_1") (pintype "passive"))
      (node (ref "R216") (pin "2") (pinfunction "2_2") (pintype "passive"))
    )
    (net (code "50") (name "Net-(C303-Pad1)") (class "Default")
      (node (ref "C303") (pin "1") (pinfunction "1_1") (pintype "passive"))
      (node (ref "L4") (pin "2") (pinfunction "2_2") (pintype "passive"))
      (node (ref "L5") (pin "1") (pinfunction "1_1") (pintype "passive"))
      (node (ref "R40") (pin "1") (pinfunction "1_1") (pintype "passive"))
      (node (ref "R43") (pin "1") (pinfunction "1_1") (pintype "passive"))
    )
    (net (code "51") (name "Net-(D2-PadA)") (class "Default")
      (node (ref "D2") (pin "A") (pinfunction "A_A") (pintype "passive"))
      (node (ref "R302") (pin "1") (pinfunction "1_1") (pintype "passive"))
      (node (ref "R303") (pin "1") (pinfunction "1_1") (pintype "passive"))
    )
    (net (code "52") (name "Net-(D301-PadC)") (class "Default")
      (node (ref "D301") (pin "C") (pinfunction "C_C") (pintype "passive"))
      (node (ref "J1") (pin "2") (pinfunction "2_2") (pintype "passive"))
      (node (ref "R301") (pin "1") (pinfunction "1_1") (pintype "passive"))
    )
    (net (code "53") (name "Net-(IC201A-I)") (class "Default")
      (node (ref "IC201") (pin "2") (pinfunction "I_2") (pintype "input"))
      (node (ref "R204") (pin "1") (pinfunction "1_1") (pintype "passive"))
      (node (ref "R42") (pin "2") (pinfunction "2_2") (pintype "passive"))
    )
    (net (code "54") (name "Net-(IC201A-O)") (class "Default")
      (node (ref "IC201") (pin "4") (pinfunction "O_4") (pintype "output"))
      (node (ref "Q201") (pin "1") (pinfunction "G_1") (pintype "passive"))
      (node (ref "R41") (pin "2") (pinfunction "2_2") (pintype "passive"))
    )
    (net (code "55") (name "Net-(IC202A-+IN)") (class "Default")
      (node (ref "C208") (pin "1") (pinfunction "1_1") (pintype "passive"))
      (node (ref "IC202") (pin "3") (pinfunction "+IN_3") (pintype "input"))
      (node (ref "R209") (pin "2") (pinfunction "2_2") (pintype "passive"))
      (node (ref "R211") (pin "1") (pinfunction "1_1") (pintype "passive"))
    )
    (net (code "56") (name "Net-(IC202A--IN)") (class "Default")
      (node (ref "C209") (pin "2") (pinfunction "2_2") (pintype "passive"))
      (node (ref "IC202") (pin "2") (pinfunction "-IN_2") (pintype "input"))
      (node (ref "R212") (pin "2") (pinfunction "2_2") (pintype "passive"))
      (node (ref "R214") (pin "2") (pinfunction "2_2") (pintype "passive"))
      (node (ref "R219") (pin "1") (pinfunction "1_1") (pintype "passive"))
    )
    (net (code "57") (name "Net-(IC202A-OUT)") (class "Default")
      (node (ref "IC202") (pin "1") (pinfunction "OUT_1") (pintype "output"))
      (node (ref "R216") (pin "1") (pinfunction "1_1") (pintype "passive"))
      (node (ref "R217") (pin "1") (pinfunction "1_1") (pintype "passive"))
    )
    (net (code "58") (name "Net-(IC202B-+IN)") (class "Default")
      (node (ref "IC202") (pin "5") (pinfunction "+IN_5") (pintype "input"))
      (node (ref "Q201") (pin "3") (pinfunction "D_3") (pintype "passive"))
      (node (ref "R207") (pin "2") (pinfunction "2_2") (pintype "passive"))
    )
    (net (code "59") (name "Net-(IC202B--IN)") (class "Default")
      (node (ref "IC202") (pin "6") (pinfunction "-IN_6") (pintype "input"))
      (node (ref "IC202") (pin "7") (pinfunction "OUT_7") (pintype "output"))
      (node (ref "R209") (pin "1") (pinfunction "1_1") (pintype "passive"))
      (node (ref "TP12") (pin "TP") (pinfunction "1_TP") (pintype "passive"))
    )
    (net (code "60") (name "Net-(IC202C-+IN)") (class "Default")
      (node (ref "IC202") (pin "10") (pinfunction "+IN_10") (pintype "input"))
      (node (ref "R203") (pin "2") (pinfunction "2_2") (pintype "passive"))
      (node (ref "R206") (pin "1") (pinfunction "1_1") (pintype "passive"))
    )
    (net (code "61") (name "Net-(IC202C--IN)") (class "Default")
      (node (ref "IC202") (pin "9") (pinfunction "-IN_9") (pintype "input"))
      (node (ref "JP202") (pin "1") (pinfunction "1_1") (pintype "passive"))
      (node (ref "R202") (pin "2") (pinfunction "2_2") (pintype "passive"))
      (node (ref "R205") (pin "1") (pinfunction "1_1") (pintype "passive"))
    )
    (net (code "62") (name "Net-(IC202C-OUT)") (class "Default")
      (node (ref "IC202") (pin "8") (pinfunction "OUT_8") (pintype "output"))
      (node (ref "JP202") (pin "2") (pinfunction "2_2") (pintype "passive"))
      (node (ref "R205") (pin "2") (pinfunction "2_2") (pintype "passive"))
      (node (ref "R207") (pin "1") (pinfunction "1_1") (pintype "passive"))
    )
    (net (code "63") (name "Net-(IC202D-+IN)") (class "Default")
      (node (ref "C201") (pin "1") (pinfunction "1_1") (pintype "passive"))
      (node (ref "IC202") (pin "12") (pinfunction "+IN_12") (pintype "input"))
      (node (ref "R201") (pin "2") (pinfunction "S_2") (pintype "passive"))
    )
    (net (code "64") (name "Net-(IC202D--IN)") (class "Default")
      (node (ref "IC202") (pin "13") (pinfunction "-IN_13") (pintype "input"))
      (node (ref "IC202") (pin "14") (pinfunction "OUT_14") (pintype "output"))
      (node (ref "R206") (pin "2") (pinfunction "2_2") (pintype "passive"))
      (node (ref "TP13") (pin "TP") (pinfunction "1_TP") (pintype "passive"))
    )
    (net (code "65") (name "Net-(J2-Pad3)") (class "Default")
      (node (ref "J2") (pin "3") (pinfunction "3_3") (pintype "passive"))
      (node (ref "R29") (pin "2") (pinfunction "2_2") (pintype "passive"))
    )
    (net (code "66") (name "Net-(J101-1)") (class "Default")
      (node (ref "C24") (pin "2") (pinfunction "2_2") (pintype "passive"))
      (node (ref "C25") (pin "2") (pinfunction "2_2") (pintype "passive"))
      (node (ref "C28") (pin "2") (pinfunction "2_2") (pintype "passive"))
      (node (ref "J101") (pin "C") (pinfunction "1_C") (pintype "passive"))
    )
    (net (code "67") (name "Net-(J102-1)") (class "Default")
      (node (ref "C26") (pin "2") (pinfunction "2_2") (pintype "passive"))
      (node (ref "C27") (pin "2") (pinfunction "2_2") (pintype "passive"))
      (node (ref "C29") (pin "2") (pinfunction "2_2") (pintype "passive"))
      (node (ref "J102") (pin "C") (pinfunction "1_C") (pintype "passive"))
    )
    (net (code "68") (name "Net-(J201-1)") (class "Default")
      (node (ref "J201") (pin "C") (pinfunction "1_C") (pintype "passive"))
      (node (ref "JP201") (pin "2") (pinfunction "2_2") (pintype "passive"))
      (node (ref "R202") (pin "1") (pinfunction "1_1") (pintype "passive"))
    )
    (net (code "69") (name "Net-(J201-GND1-PadG1)") (class "Default")
      (node (ref "J201") (pin "G1") (pinfunction "GND1_G1") (pintype "power_in"))
      (node (ref "J201") (pin "G2") (pinfunction "GND1_G2") (pintype "power_in"))
      (node (ref "J201") (pin "G3") (pinfunction "GND1_G3") (pintype "power_in"))
      (node (ref "J201") (pin "G4") (pinfunction "GND1_G4") (pintype "power_in"))
      (node (ref "JP201") (pin "1") (pinfunction "1_1") (pintype "passive"))
      (node (ref "R203") (pin "1") (pinfunction "1_1") (pintype "passive"))
    )
    (net (code "70") (name "Net-(J202-1)") (class "Default")
      (node (ref "J202") (pin "C") (pinfunction "1_C") (pintype "passive"))
      (node (ref "R42") (pin "1") (pinfunction "1_1") (pintype "passive"))
    )
    (net (code "71") (name "Net-(LED1-C)") (class "Default")
      (node (ref "LED1") (pin "K") (pinfunction "C_K") (pintype "passive"))
      (node (ref "R28") (pin "1") (pinfunction "1_1") (pintype "passive"))
    )
    (net (code "72") (name "Net-(LED2-C)") (class "Default")
      (node (ref "LED2") (pin "K") (pinfunction "C_K") (pintype "passive"))
      (node (ref "R27") (pin "1") (pinfunction "1_1") (pintype "passive"))
    )
    (net (code "73") (name "Net-(LED3-C)") (class "Default")
      (node (ref "LED3") (pin "K") (pinfunction "C_K") (pintype "passive"))
      (node (ref "R41") (pin "1") (pinfunction "1_1") (pintype "passive"))
    )
    (net (code "74") (name "Net-(R217-Pad2)") (class "Default")
      (node (ref "R217") (pin "2") (pinfunction "2_2") (pintype "passive"))
      (node (ref "R218") (pin "1") (pinfunction "1_1") (pintype "passive"))
      (node (ref "T201") (pin "B") (pinfunction "B_B") (pintype "passive"))
      (node (ref "T202") (pin "B") (pinfunction "B_B") (pintype "passive"))
    )
    (net (code "75") (name "Net-(T1-F1)") (class "Default")
      (node (ref "R31") (pin "1") (pinfunction "1_1") (pintype "passive"))
      (node (ref "T1") (pin "12") (pinfunction "F1_12") (pintype "passive"))
      (node (ref "T1") (pin "2") (pinfunction "S2_2") (pintype "passive"))
    )
    (net (code "76") (name "Net-(T1-F4)") (class "Default")
      (node (ref "T1") (pin "3") (pinfunction "S3_3") (pintype "passive"))
      (node (ref "T1") (pin "9") (pinfunction "F4_9") (pintype "passive"))
    )
    (net (code "77") (name "Net-(T1-F5)") (class "Default")
      (node (ref "C28") (pin "1") (pinfunction "1_1") (pintype "passive"))
      (node (ref "T1") (pin "4") (pinfunction "S4_4") (pintype "passive"))
      (node (ref "T1") (pin "8") (pinfunction "F5_8") (pintype "passive"))
    )
    (net (code "78") (name "Net-(T1-F6)") (class "Default")
      (node (ref "C24") (pin "1") (pinfunction "1_1") (pintype "passive"))
      (node (ref "T1") (pin "5") (pinfunction "S5_5") (pintype "passive"))
      (node (ref "T1") (pin "7") (pinfunction "F6_7") (pintype "passive"))
    )
    (net (code "79") (name "Net-(T1-S6)") (class "Default")
      (node (ref "C25") (pin "1") (pinfunction "1_1") (pintype "passive"))
      (node (ref "T1") (pin "6") (pinfunction "S6_6") (pintype "passive"))
    )
    (net (code "80") (name "Net-(T2-F1)") (class "Default")
      (node (ref "C27") (pin "1") (pinfunction "1_1") (pintype "passive"))
      (node (ref "T2") (pin "12") (pinfunction "F1_12") (pintype "passive"))
      (node (ref "T2") (pin "2") (pinfunction "S2_2") (pintype "passive"))
    )
    (net (code "81") (name "Net-(T2-F2)") (class "Default")
      (node (ref "C29") (pin "1") (pinfunction "1_1") (pintype "passive"))
      (node (ref "T2") (pin "11") (pinfunction "F2_11") (pintype "passive"))
      (node (ref "T2") (pin "3") (pinfunction "S3_3") (pintype "passive"))
    )
    (net (code "82") (name "Net-(T2-F3)") (class "Default")
      (node (ref "T2") (pin "10") (pinfunction "F3_10") (pintype "passive"))
      (node (ref "T2") (pin "4") (pinfunction "S4_4") (pintype "passive"))
    )
    (net (code "83") (name "Net-(T2-F6)") (class "Default")
      (node (ref "R30") (pin "2") (pinfunction "2_2") (pintype "passive"))
      (node (ref "T2") (pin "5") (pinfunction "S5_5") (pintype "passive"))
      (node (ref "T2") (pin "7") (pinfunction "F6_7") (pintype "passive"))
    )
    (net (code "84") (name "Net-(T2-S1)") (class "Default")
      (node (ref "C26") (pin "1") (pinfunction "1_1") (pintype "passive"))
      (node (ref "T2") (pin "1") (pinfunction "S1_1") (pintype "passive"))
    )
    (net (code "85") (name "Net-(X1A-KL)") (class "Default")
      (node (ref "J1") (pin "1") (pinfunction "1_1") (pintype "passive"))
      (node (ref "X1") (pin "1") (pinfunction "KL_1") (pintype "passive"))
    )
    (net (code "86") (name "VB") (class "Default")
      (node (ref "C17") (pin "1") (pinfunction "1_1") (pintype "passive"))
      (node (ref "C18") (pin "1") (pinfunction "1_1") (pintype "passive"))
      (node (ref "C19") (pin "1") (pinfunction "1_1") (pintype "passive"))
      (node (ref "C20") (pin "1") (pinfunction "1_1") (pintype "passive"))
      (node (ref "C21") (pin "1") (pinfunction "1_1") (pintype "passive"))
      (node (ref "C304") (pin "1") (pinfunction "1_1") (pintype "passive"))
      (node (ref "L5") (pin "2") (pinfunction "2_2") (pintype "passive"))
      (node (ref "L6") (pin "2") (pinfunction "2_2") (pintype "passive"))
      (node (ref "L7") (pin "2") (pinfunction "2_2") (pintype "passive"))
      (node (ref "R30") (pin "1") (pinfunction "1_1") (pintype "passive"))
      (node (ref "R40") (pin "2") (pinfunction "2_2") (pintype "passive"))
      (node (ref "R43") (pin "2") (pinfunction "2_2") (pintype "passive"))
    )
    (net (code "87") (name "unconnected-(J2-Pad4)") (class "Default")
      (node (ref "J2") (pin "4") (pinfunction "4_4") (pintype "passive"))
    )
  )
)
